# design.net
KiCad netlist of a schematic drawn in Altium Designer
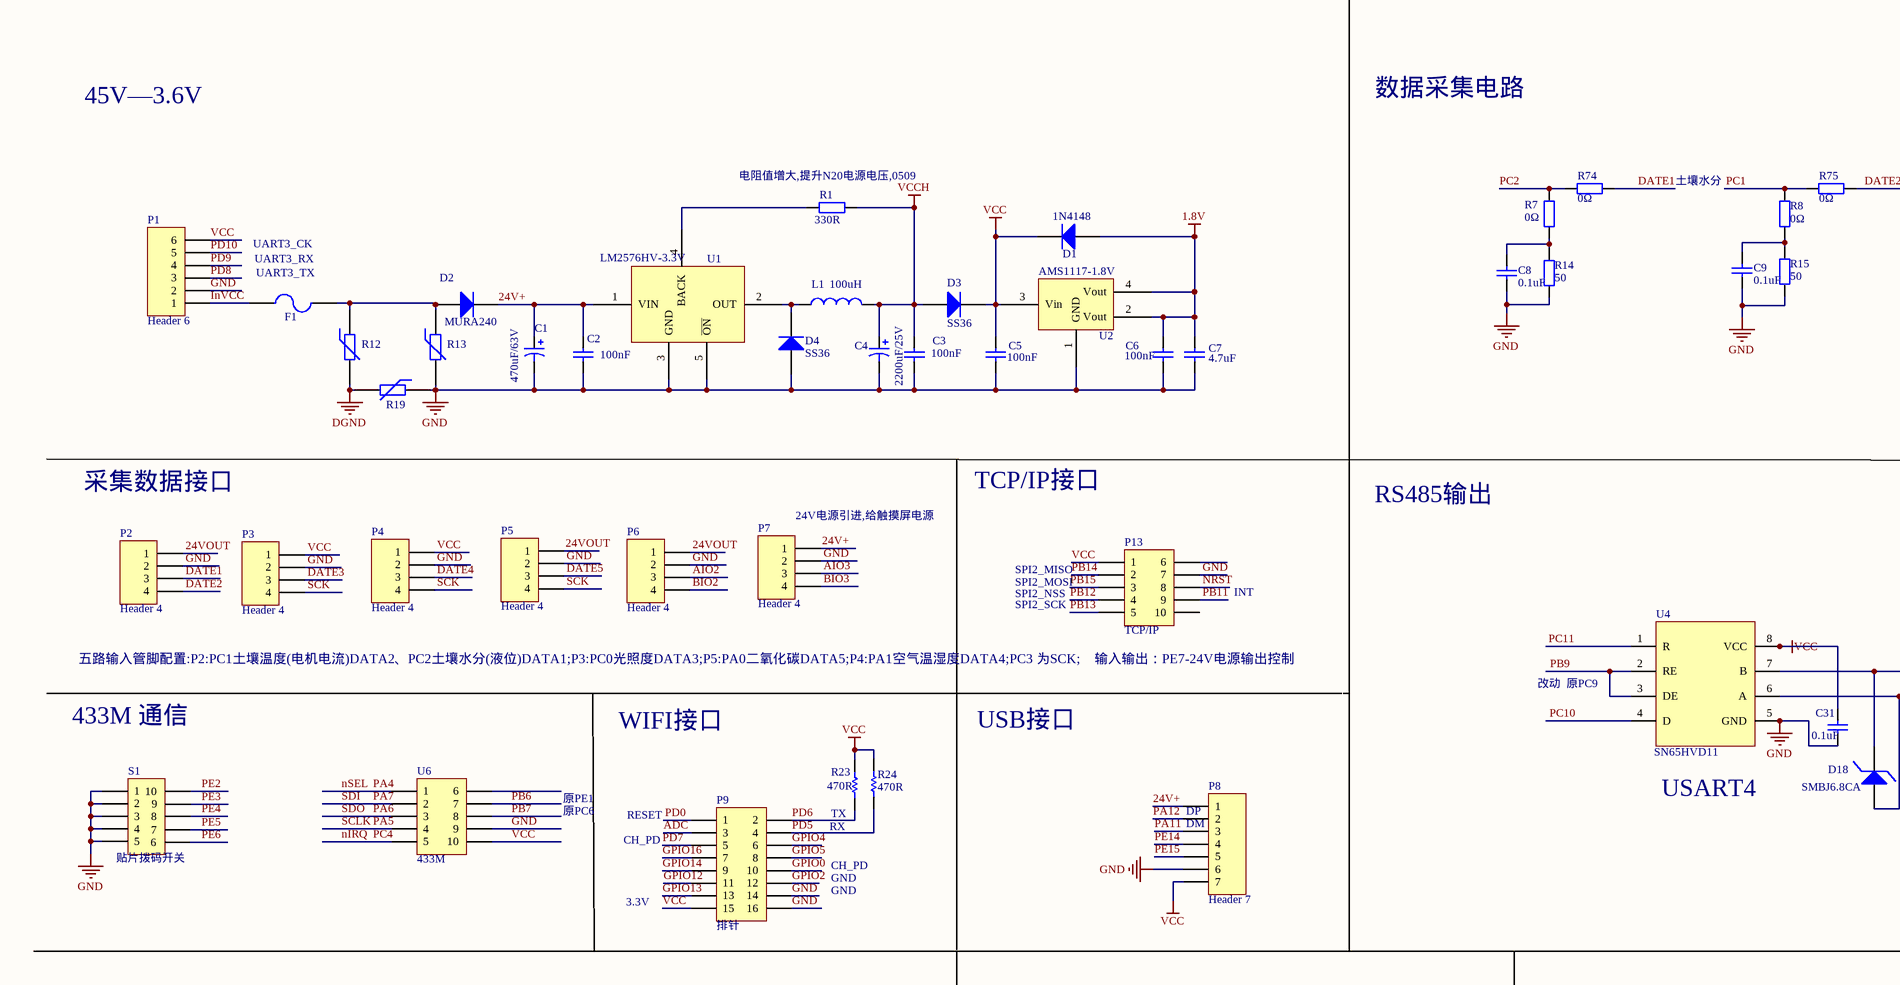
[diagram p0: 边缘网关一体.SchDoc, top left]
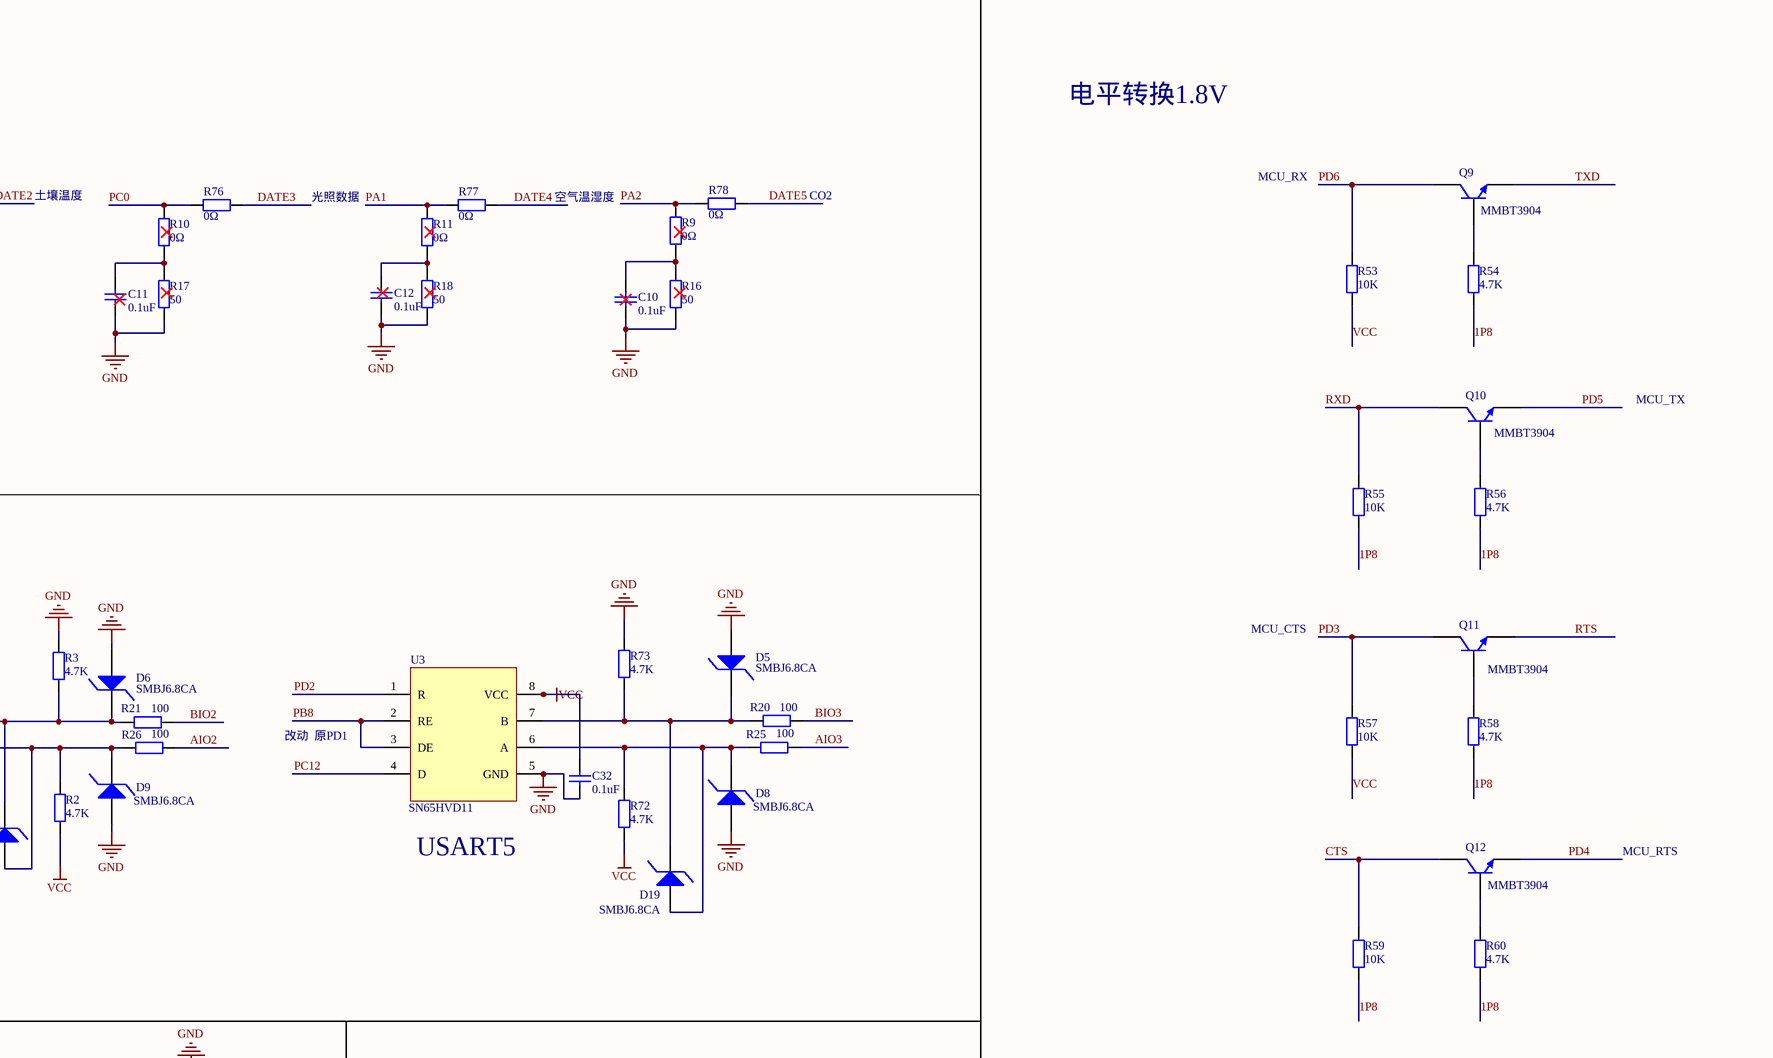
[diagram p1: 边缘网关一体.SchDoc, top right]
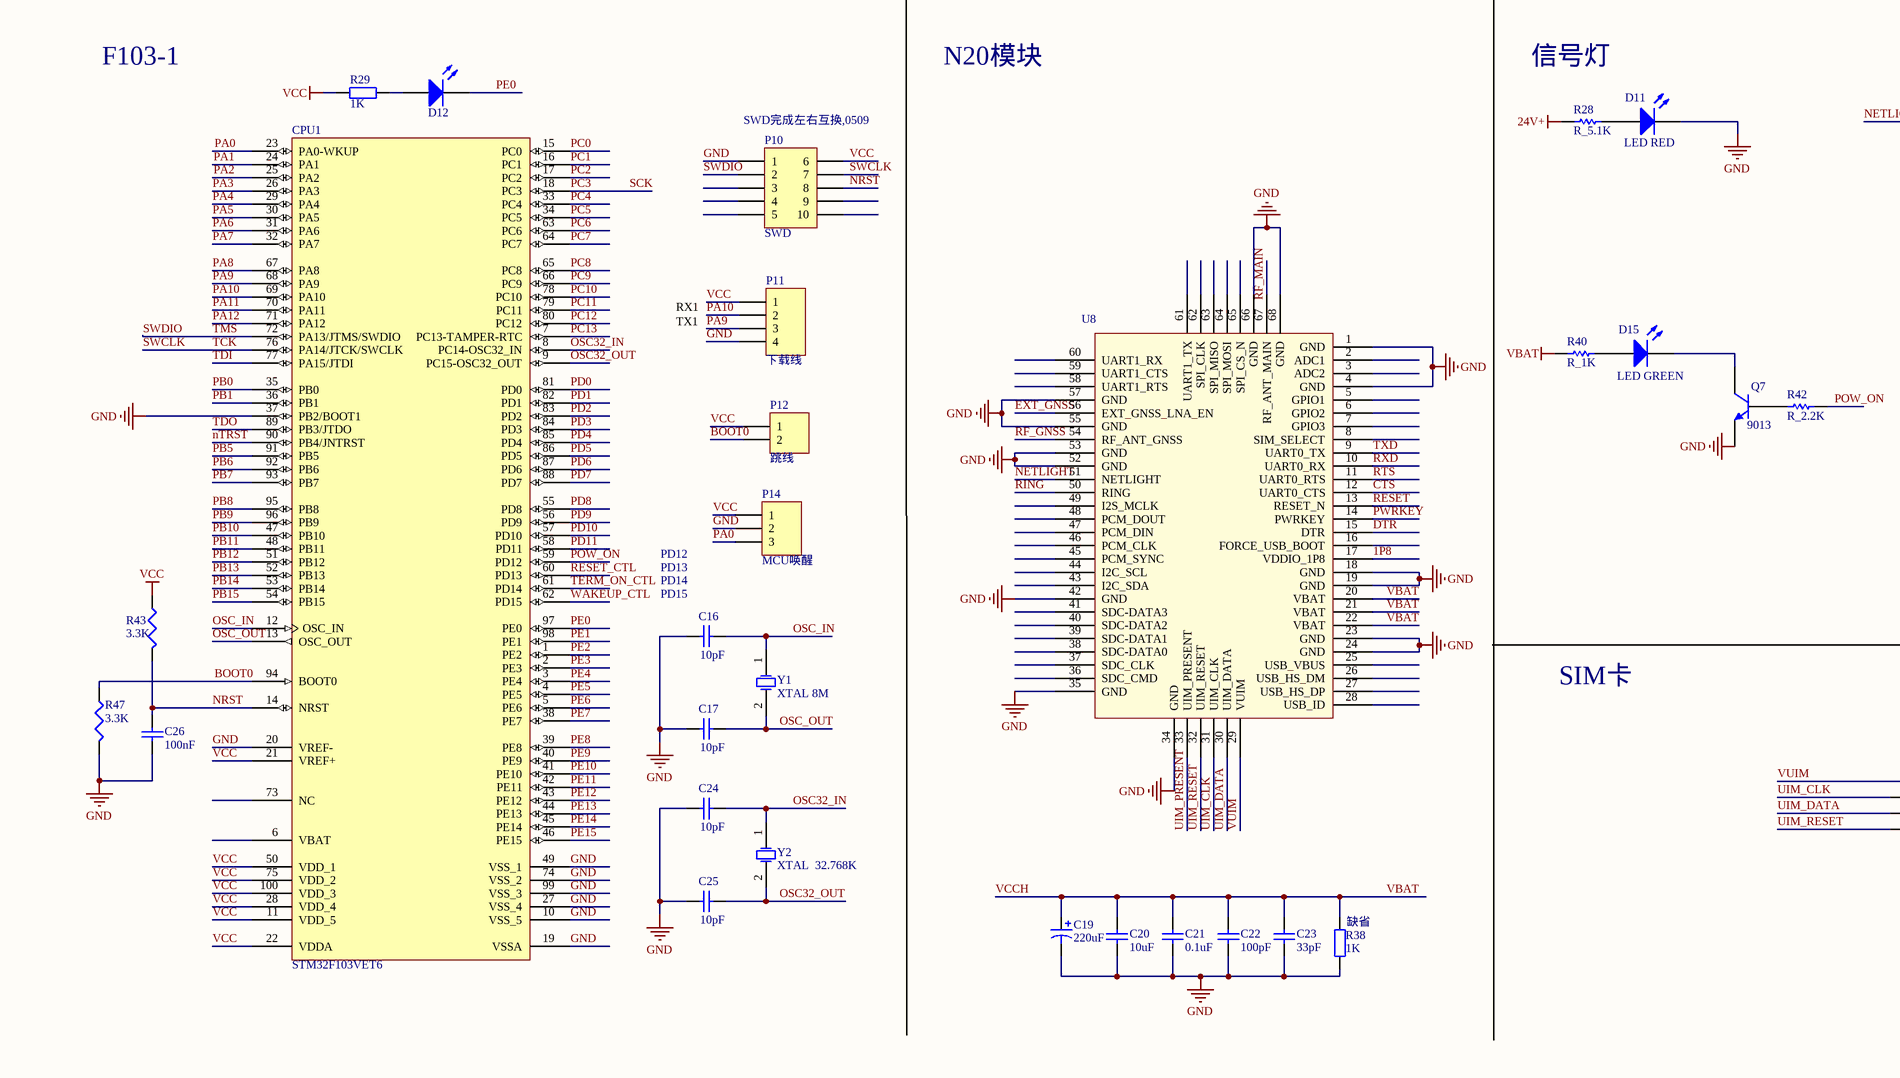
[diagram p2: 边缘网关一体.SchDoc, bottom left]
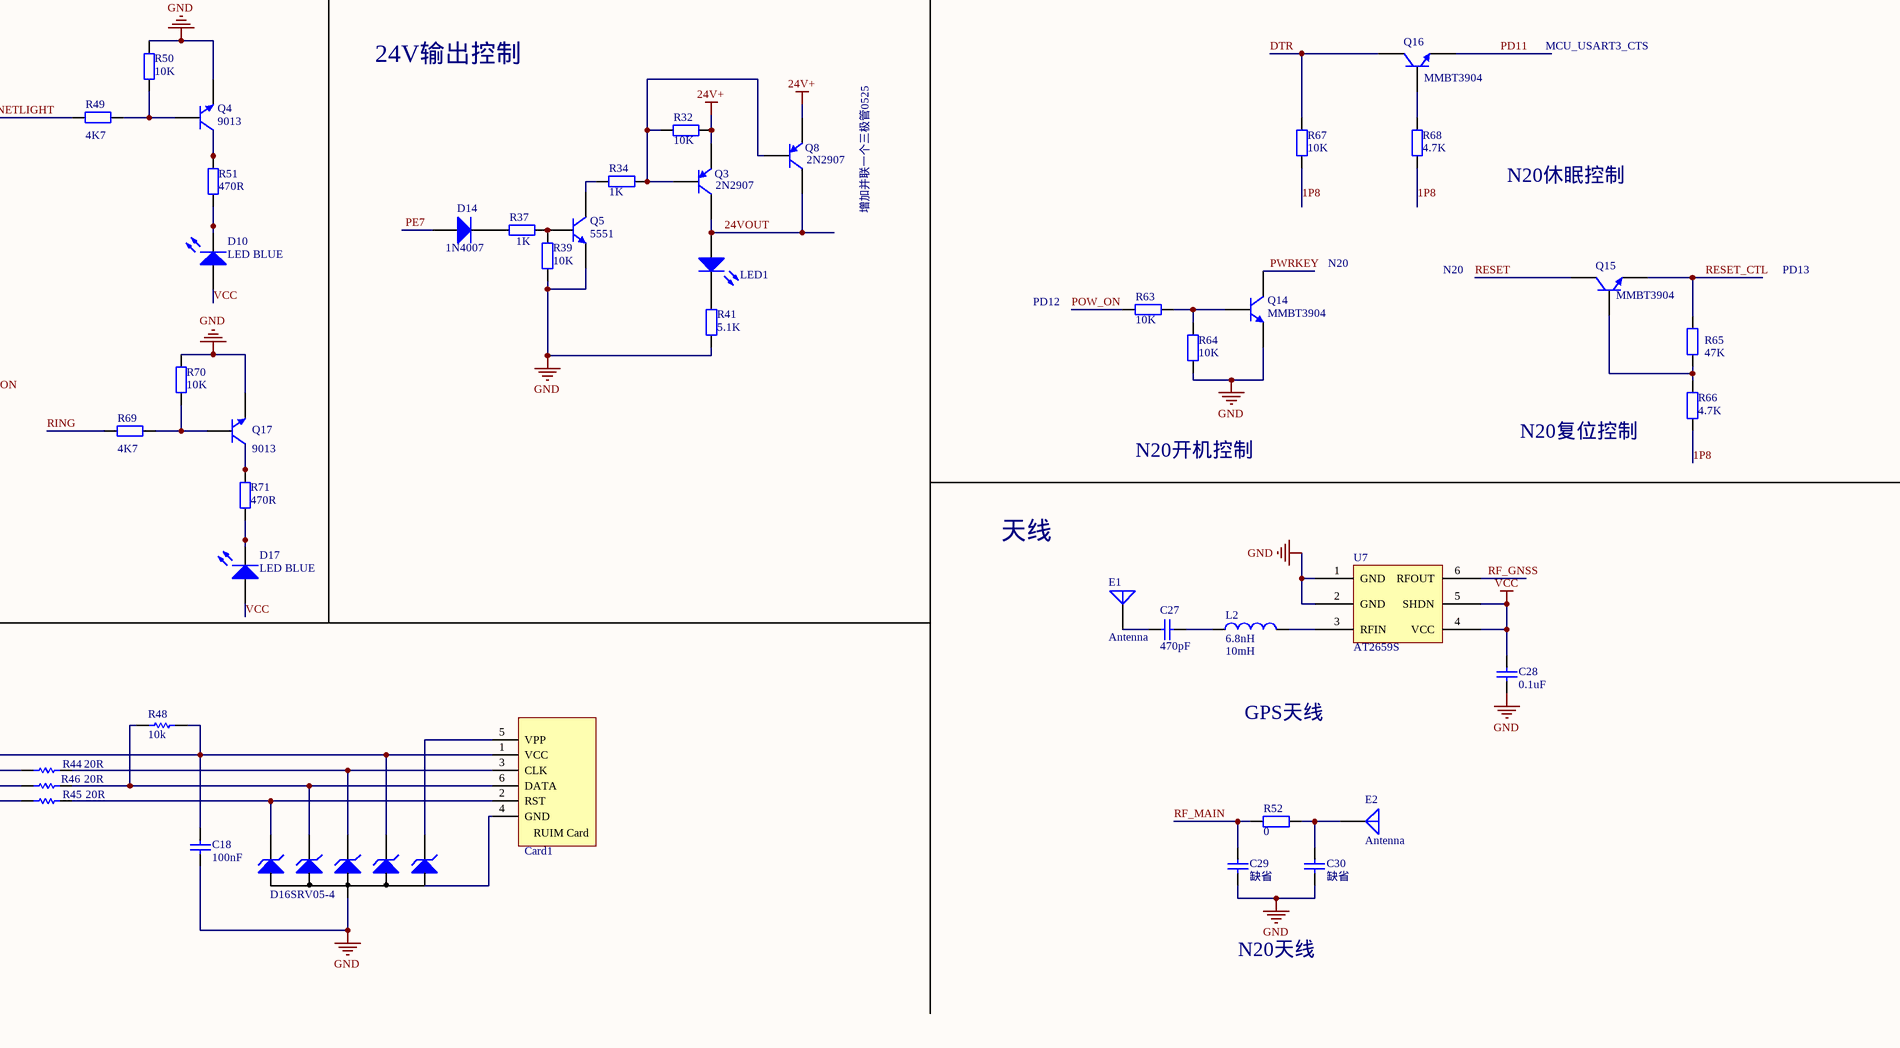
[diagram p3: 边缘网关一体.SchDoc, bottom right]

(export (version "E")
  (design (tool "Eeschema 10.0.6"))
  (components
    (comp (ref "C1")
      (value "470uF/63V")
      (footprint "C470UF50V-H")
      (description "插件 电解电容 13*21")
      (fields (field (name "Comment") "C_470uF/63V") (field (name "PUBLISHER") "Altium Limited"))
      (libsource (lib "Miscellaneous Devices") (part "Cap Pol1"))
    )
    (comp (ref "C2")
      (value "100nF")
      (footprint "0805")
      (description "贴片电容 0603")
      (fields (field (name "Comment") "C_0.1uF") (field (name "PUBLISHER") "Altium Limited"))
      (libsource (lib "Miscellaneous Devices") (part "Cap"))
    )
    (comp (ref "C3")
      (value "100nF")
      (footprint "0603")
      (description "贴片电容 0603")
      (fields (field (name "Comment") "C_0.1uF") (field (name "PUBLISHER") "Altium Limited"))
      (libsource (lib "Miscellaneous Devices") (part "Cap"))
    )
    (comp (ref "C4")
      (value "2200uF/25V")
      (footprint "C470UF50V-H")
      (description "插件 体积13*20mm")
      (fields (field (name "PUBLISHER") "Altium Limited"))
      (libsource (lib "Miscellaneous Devices") (part "Cap Pol1"))
    )
    (comp (ref "C5")
      (value "100nF")
      (footprint "0805")
      (description "贴片电容 0603")
      (fields (field (name "PUBLISHER") "Altium Limited"))
      (libsource (lib "Miscellaneous Devices") (part "Cap"))
    )
    (comp (ref "C6")
      (value "100nF")
      (footprint "0603")
      (description "贴片电容 0603")
      (fields (field (name "PUBLISHER") "Altium Limited"))
      (libsource (lib "Miscellaneous Devices") (part "Cap"))
    )
    (comp (ref "C7")
      (value "4.7uF")
      (footprint "0805")
      (description "贴片电容 0603")
      (libsource (lib "MyMiscellaneousDevices") (part "Cap"))
    )
    (comp (ref "C8")
      (value "0.1uF")
      (footprint "0603")
      (description "贴片电容 0603")
      (fields (field (name "Comment") "C_0.1uF") (field (name "PUBLISHER") "Altium Limited"))
      (libsource (lib "Miscellaneous Devices") (part "Cap"))
    )
    (comp (ref "C9")
      (value "0.1uF")
      (footprint "0603")
      (description "贴片电容 0603")
      (fields (field (name "Comment") "C_0.1uF") (field (name "PUBLISHER") "Altium Limited"))
      (libsource (lib "Miscellaneous Devices") (part "Cap"))
    )
    (comp (ref "C10")
      (value "0.1uF")
      (footprint "0603")
      (description "贴片电容 0603")
      (fields (field (name "Comment") "C_0.1uF") (field (name "PUBLISHER") "Altium Limited"))
      (libsource (lib "Miscellaneous Devices") (part "Cap"))
    )
    (comp (ref "C11")
      (value "0.1uF")
      (footprint "0603")
      (description "贴片电容 0603")
      (fields (field (name "Comment") "C_0.1uF") (field (name "PUBLISHER") "Altium Limited"))
      (libsource (lib "Miscellaneous Devices") (part "Cap"))
    )
    (comp (ref "C12")
      (value "0.1uF")
      (footprint "0603")
      (description "贴片电容 0603")
      (fields (field (name "Comment") "C_0.1uF") (field (name "PUBLISHER") "Altium Limited"))
      (libsource (lib "Miscellaneous Devices") (part "Cap"))
    )
    (comp (ref "C16")
      (value "10pF")
      (footprint "0603")
      (description "贴片电容 0603")
      (fields (field (name "Comment") "C_10pF") (field (name "PUBLISHER") "Altium Limited"))
      (libsource (lib "Miscellaneous Devices") (part "Cap"))
    )
    (comp (ref "C17")
      (value "10pF")
      (footprint "0603")
      (description "贴片电容 0603")
      (fields (field (name "Comment") "C_10pF") (field (name "PUBLISHER") "Altium Limited"))
      (libsource (lib "Miscellaneous Devices") (part "Cap"))
    )
    (comp (ref "C18")
      (value "100nF")
      (footprint "0805")
      (description "贴片电容 0603")
      (fields (field (name "Comment") "C_0.1uF") (field (name "PUBLISHER") "Altium Limited"))
      (libsource (lib "边缘网关一体17KF4") (part "Cap"))
    )
    (comp (ref "C19")
      (value "220uF")
      (footprint "1206")
      (description "Polarized Capacitor (Radial)")
      (fields (field (name "PUBLISHER") "Altium Limited"))
      (libsource (lib "Miscellaneous Devices") (part "Cap Pol1"))
    )
    (comp (ref "C20")
      (value "10uF")
      (footprint "0603")
      (description "贴片电容 0603")
      (fields (field (name "Comment") "C_0.1uF") (field (name "PUBLISHER") "Altium Limited"))
      (libsource (lib "Miscellaneous Devices") (part "Cap"))
    )
    (comp (ref "C21")
      (value "0.1uF")
      (footprint "0603")
      (description "贴片电容 0603")
      (fields (field (name "Comment") "C_0.1uF") (field (name "PUBLISHER") "Altium Limited"))
      (libsource (lib "Miscellaneous Devices") (part "Cap"))
    )
    (comp (ref "C22")
      (value "100pF")
      (footprint "0603")
      (description "贴片电容 0603")
      (fields (field (name "Comment") "C_0.1uF") (field (name "PUBLISHER") "Altium Limited"))
      (libsource (lib "Miscellaneous Devices") (part "Cap"))
    )
    (comp (ref "C23")
      (value "33pF")
      (footprint "0603")
      (description "贴片电容 0603")
      (fields (field (name "Comment") "C_0.1uF") (field (name "PUBLISHER") "Altium Limited"))
      (libsource (lib "Miscellaneous Devices") (part "Cap"))
    )
    (comp (ref "C24")
      (value "10pF")
      (footprint "0603")
      (description "贴片电容 0603")
      (fields (field (name "Comment") "C_10pF") (field (name "PUBLISHER") "Altium Limited"))
      (libsource (lib "Miscellaneous Devices") (part "Cap"))
    )
    (comp (ref "C25")
      (value "10pF")
      (footprint "0603")
      (description "贴片电容 0603")
      (fields (field (name "Comment") "C_10pF") (field (name "PUBLISHER") "Altium Limited"))
      (libsource (lib "Miscellaneous Devices") (part "Cap"))
    )
    (comp (ref "C26")
      (value "100nF")
      (footprint "0603")
      (description "贴片电容 0603")
      (fields (field (name "Comment") "C_100nF") (field (name "PUBLISHER") "Altium Limited"))
      (libsource (lib "Miscellaneous Devices") (part "Cap"))
    )
    (comp (ref "C27")
      (value "470pF")
      (footprint "1608[0603]")
      (description "Capacitor")
      (fields (field (name "PUBLISHER") "Altium Limited"))
      (libsource (lib "Miscellaneous Devices") (part "Cap"))
    )
    (comp (ref "C28")
      (value "0.1uF")
      (footprint "1608[0603]")
      (description "Capacitor")
      (fields (field (name "PUBLISHER") "Altium Limited"))
      (libsource (lib "Miscellaneous Devices") (part "Cap"))
    )
    (comp (ref "C29")
      (value "缺省")
      (footprint "0603")
      (description "Capacitor")
      (fields (field (name "PUBLISHER") "Altium Limited"))
      (libsource (lib "Miscellaneous Devices") (part "Cap"))
    )
    (comp (ref "C30")
      (value "缺省")
      (footprint "0603")
      (description "Capacitor")
      (fields (field (name "PUBLISHER") "Altium Limited"))
      (libsource (lib "Miscellaneous Devices") (part "Cap"))
    )
    (comp (ref "C31")
      (value "0.1uF")
      (footprint "0603")
      (description "Capacitor")
      (fields (field (name "PUBLISHER") "Altium Limited"))
      (libsource (lib "Miscellaneous Devices") (part "Cap"))
    )
    (comp (ref "C32")
      (value "0.1uF")
      (footprint "0603")
      (description "Capacitor")
      (fields (field (name "PUBLISHER") "Altium Limited"))
      (libsource (lib "Miscellaneous Devices") (part "Cap"))
    )
    (comp (ref "Card1") (value "Card") (footprint "SIM") (libsource (lib "ZDHH") (part "Card")))
    (comp (ref "CPU1")
      (value "STM32F103VET6")
      (footprint "LQFP100_N")
      (description "贴片ARM芯片")
      (fields (field (name "PUBLISHER") "Altium Limited"))
      (libsource (lib "ST Microcontroller 32-Bit STM32") (part "STM32F103VBT6"))
    )
    (comp (ref "D1")
      (value "1N4148")
      (footprint "1206")
      (description "贴片二极管 M7")
      (fields (field (name "PUBLISHER") "Altium Limited"))
      (libsource (lib "") (part "Diode_1"))
    )
    (comp (ref "D2")
      (value "MURA240")
      (footprint "1N4007-M7")
      (description "贴片二极管 M7")
      (fields (field (name "PUBLISHER") "Altium Limited"))
      (libsource (lib "Miscellaneous Devices") (part "Diode"))
    )
    (comp (ref "D3")
      (value "SS36")
      (footprint "1N4007-M7")
      (description "贴片二极管 SMA")
      (fields (field (name "PUBLISHER") "Altium Limited"))
      (libsource (lib "Miscellaneous Devices") (part "Diode 1N4007"))
    )
    (comp (ref "D4")
      (value "SS36")
      (footprint "1N4007-M7")
      (description "贴片二极管 SMA")
      (fields (field (name "PUBLISHER") "Altium Limited"))
      (libsource (lib "Miscellaneous Devices") (part "Diode 1N4007"))
    )
    (comp (ref "D5")
      (value "SMBJ6.8CA")
      (footprint "DO-214AB")
      (description "贴片双向瞬变抑制二极管 D0-214AA")
      (libsource (lib "User Library") (part "SMBJ6.8CA"))
    )
    (comp (ref "D6")
      (value "SMBJ6.8CA")
      (footprint "DO-214AB")
      (description "贴片双向瞬变抑制二极管 D0-214AA")
      (libsource (lib "User Library") (part "SMBJ6.8CA"))
    )
    (comp (ref "D8")
      (value "SMBJ6.8CA")
      (footprint "DO-214AB")
      (description "贴片双向瞬变抑制二极管 D0-214AA")
      (libsource (lib "User Library") (part "SMBJ6.8CA"))
    )
    (comp (ref "D9")
      (value "SMBJ6.8CA")
      (footprint "DO-214AB")
      (description "贴片双向瞬变抑制二极管 D0-214AA")
      (libsource (lib "User Library") (part "SMBJ6.8CA"))
    )
    (comp (ref "D10")
      (value "LED BLUE")
      (footprint "LED-3mm")
      (description "插件 发光二极管 5mm 红发红光")
      (fields (field (name "PUBLISHER") "Altium Limited"))
      (libsource (lib "Miscellaneous Devices") (part "LED0"))
    )
    (comp (ref "D11")
      (value "LED RED")
      (footprint "LED-3mm")
      (description "插件 发光二极管 5mm 红发红光")
      (fields (field (name "PUBLISHER") "Altium Limited"))
      (libsource (lib "Miscellaneous Devices") (part "LED0"))
    )
    (comp (ref "D12")
      (value "Green")
      (footprint "0603")
      (description "贴片发光二极管 0603 绿色")
      (libsource (lib "Schlib-user") (part "LED 3mm"))
    )
    (comp (ref "D14")
      (value "1N4007")
      (footprint "1N4007-M7")
      (description "1 Amp General Purpose Rectifier")
      (fields (field (name "PUBLISHER") "Altium Limited"))
      (libsource (lib "Miscellaneous Devices") (part "Diode 1N4007"))
    )
    (comp (ref "D15")
      (value "LED GREEN")
      (footprint "LED-3mm")
      (description "插件 发光二极管 5mm 绿发绿光")
      (fields (field (name "PUBLISHER") "Altium Limited"))
      (libsource (lib "Miscellaneous Devices") (part "LED0"))
    )
    (comp (ref "D16")
      (value "SRV05-4")
      (footprint "SOT23-6")
      (description "SOT363")
      (fields (field (name "PUBLISHER") "Altium Limited"))
      (libsource (lib "SCHLIB") (part "SMF05C"))
    )
    (comp (ref "D17")
      (value "LED BLUE")
      (footprint "LED-3mm")
      (description "插件 发光二极管 5mm 红发红光")
      (fields (field (name "PUBLISHER") "Altium Limited"))
      (libsource (lib "Miscellaneous Devices") (part "LED0"))
    )
    (comp (ref "D18")
      (value "SMBJ6.8CA")
      (footprint "DO-214AB")
      (description "贴片双向瞬变抑制二极管 D0-214AA")
      (libsource (lib "User Library") (part "SMBJ6.8CA"))
    )
    (comp (ref "D19")
      (value "SMBJ6.8CA")
      (footprint "DO-214AB")
      (description "贴片双向瞬变抑制二极管 D0-214AA")
      (libsource (lib "User Library") (part "SMBJ6.8CA"))
    )
    (comp (ref "E1")
      (value "Antenna")
      (footprint "IPX")
      (description "Generic Antenna")
      (fields (field (name "PUBLISHER") "Altium Limited"))
      (libsource (lib "Miscellaneous Devices") (part "Antenna"))
    )
    (comp (ref "E2")
      (value "Antenna")
      (footprint "IPX")
      (description "Generic Antenna")
      (fields (field (name "PUBLISHER") "Altium Limited"))
      (libsource (lib "Miscellaneous Devices") (part "Antenna"))
    )
    (comp (ref "F1")
      (value "自恢复保险丝")
      (footprint "1812")
      (description "1812 1.1A 33V")
      (fields (field (name "PUBLISHER") "Altium Limited"))
      (libsource (lib "Miscellaneous Devices") (part "Fuse 2"))
    )
    (comp (ref "L1")
      (value "100uH")
      (footprint "L101")
      (description "贴片电感 12*12*7mm 100uH")
      (fields (field (name "Comment") "贴片电感") (field (name "PUBLISHER") "Altium Limited"))
      (libsource (lib "Miscellaneous Devices") (part "Inductor"))
    )
    (comp (ref "L2")
      (value "6.8nH")
      (footprint "L0603")
      (description "Inductor")
      (fields (field (name "ALTIUM_VALUE") "10mH") (field (name "PUBLISHER") "Altium Limited"))
      (libsource (lib "Miscellaneous Devices") (part "Inductor"))
    )
    (comp (ref "LED1")
      (value "LED 3mm")
      (footprint "0603")
      (description "LED_R")
      (libsource (lib "Schlib-user") (part "LED 3mm"))
    )
    (comp (ref "P1")
      (value "Header 6")
      (footprint "P6HEADER:PCBComponent_1")
      (description "Header, 6-Pin")
      (fields (field (name "PUBLISHER") "Altium Limited"))
      (libsource (lib "Miscellaneous Connectors") (part "Header 6"))
    )
    (comp (ref "P2")
      (value "Header 4")
      (footprint "HDR1X4")
      (description "Header, 4-Pin")
      (fields (field (name "PUBLISHER") "Altium Limited"))
      (libsource (lib "Miscellaneous Connectors") (part "Header 4"))
    )
    (comp (ref "P3")
      (value "Header 4")
      (footprint "HDR1X4")
      (description "Header, 4-Pin")
      (fields (field (name "PUBLISHER") "Altium Limited"))
      (libsource (lib "Miscellaneous Connectors") (part "Header 4"))
    )
    (comp (ref "P4")
      (value "Header 4")
      (footprint "HDR1X4")
      (description "Header, 4-Pin")
      (fields (field (name "PUBLISHER") "Altium Limited"))
      (libsource (lib "Miscellaneous Connectors") (part "Header 4"))
    )
    (comp (ref "P5")
      (value "Header 4")
      (footprint "HDR1X4")
      (description "Header, 4-Pin")
      (fields (field (name "PUBLISHER") "Altium Limited"))
      (libsource (lib "Miscellaneous Connectors") (part "Header 4"))
    )
    (comp (ref "P6")
      (value "Header 4")
      (footprint "HDR1X4")
      (description "Header, 4-Pin")
      (fields (field (name "PUBLISHER") "Altium Limited"))
      (libsource (lib "Miscellaneous Connectors") (part "Header 4"))
    )
    (comp (ref "P7")
      (value "Header 4")
      (footprint "HDR1X4")
      (description "Header, 4-Pin")
      (fields (field (name "PUBLISHER") "Altium Limited"))
      (libsource (lib "Miscellaneous Connectors") (part "Header 4"))
    )
    (comp (ref "P8")
      (value "Header 7")
      (footprint "USB2")
      (description "Header, 7-Pin")
      (fields (field (name "PUBLISHER") "Altium Limited"))
      (libsource (lib "Miscellaneous Connectors") (part "Header 7"))
    )
    (comp (ref "P9")
      (value "排针")
      (footprint "WIFI2")
      (description "插件 8P 间距2mm")
      (fields (field (name "PUBLISHER") "Altium Limited"))
      (libsource (lib "Miscellaneous Connectors") (part "Header 8X2"))
    )
    (comp (ref "P10")
      (value "SWD")
      (footprint "HDR2X5_CEN")
      (description "Header, 5-Pin, Dual row")
      (fields (field (name "PUBLISHER") "Altium Limited"))
      (libsource (lib "Miscellaneous Connectors") (part "Header 5X2A"))
    )
    (comp (ref "P11")
      (value "下载线")
      (footprint "HDR1X4")
      (description "Header, 4-Pin")
      (fields (field (name "PUBLISHER") "Altium Limited"))
      (libsource (lib "") (part "Header 4_1"))
    )
    (comp (ref "P12")
      (value "跳线")
      (footprint "HDR1X2")
      (description "Header, 2-Pin")
      (fields (field (name "PUBLISHER") "Altium Limited"))
      (libsource (lib "Miscellaneous Connectors") (part "Header 2"))
    )
    (comp (ref "P13")
      (value "TCP/IP")
      (footprint "TCP-IP")
      (description "Header, 5-Pin, Dual row")
      (fields (field (name "PUBLISHER") "Altium Limited"))
      (libsource (lib "Miscellaneous Connectors") (part "Header 5X2A"))
    )
    (comp (ref "P14")
      (value "MCU唤醒")
      (footprint "HDR1X3")
      (description "Header, 3-Pin")
      (fields (field (name "PUBLISHER") "Altium Limited"))
      (libsource (lib "Miscellaneous Connectors") (part "Header 3"))
    )
    (comp (ref "Q3")
      (value "2N2907")
      (footprint "Q")
      (description "PNP Bipolar Transistor")
      (fields (field (name "PUBLISHER") "Altium Limited"))
      (libsource (lib "Miscellaneous Devices") (part "PNP"))
    )
    (comp (ref "Q4")
      (value "9013")
      (footprint "SOT-23")
      (description "贴片三极管MMBT5551 SOT-23")
      (fields (field (name "PUBLISHER") "Altium Limited"))
      (libsource (lib "MyMiscellaneousDevices") (part "NPN"))
    )
    (comp (ref "Q5")
      (value "5551")
      (footprint "Q")
      (description "2N3904")
      (fields (field (name "PUBLISHER") "Altium Limited"))
      (libsource (lib "Miscellaneous Devices") (part "2N3904"))
    )
    (comp (ref "Q7")
      (value "9013")
      (footprint "SOT-23")
      (description "贴片三极管MMBT5551 SOT-23")
      (fields (field (name "PUBLISHER") "Altium Limited"))
      (libsource (lib "MyMiscellaneousDevices") (part "NPN"))
    )
    (comp (ref "Q8")
      (value "2N2907")
      (footprint "Q")
      (description "PNP Bipolar Transistor")
      (fields (field (name "PUBLISHER") "Altium Limited"))
      (libsource (lib "Miscellaneous Devices") (part "PNP"))
    )
    (comp (ref "Q9")
      (value "MMBT3904")
      (footprint "SOT23_N")
      (description "NPN Switching Transistor")
      (fields (field (name "PUBLISHER") "Altium Limited"))
      (libsource (lib "Philips Discrete BJT - Low Power") (part "MMBT3904"))
    )
    (comp (ref "Q10")
      (value "MMBT3904")
      (footprint "SOT23_N")
      (description "NPN Switching Transistor")
      (fields (field (name "PUBLISHER") "Altium Limited"))
      (libsource (lib "Philips Discrete BJT - Low Power") (part "MMBT3904"))
    )
    (comp (ref "Q11")
      (value "MMBT3904")
      (footprint "SOT23_N")
      (description "NPN Switching Transistor")
      (fields (field (name "PUBLISHER") "Altium Limited"))
      (libsource (lib "Philips Discrete BJT - Low Power") (part "MMBT3904"))
    )
    (comp (ref "Q12")
      (value "MMBT3904")
      (footprint "SOT23_N")
      (description "NPN Switching Transistor")
      (fields (field (name "PUBLISHER") "Altium Limited"))
      (libsource (lib "Philips Discrete BJT - Low Power") (part "MMBT3904"))
    )
    (comp (ref "Q14")
      (value "MMBT3904")
      (footprint "SOT23_N")
      (description "NPN Switching Transistor")
      (fields (field (name "PUBLISHER") "Altium Limited"))
      (libsource (lib "Philips Discrete BJT - Low Power") (part "MMBT3904"))
    )
    (comp (ref "Q15")
      (value "MMBT3904")
      (footprint "SOT23_N")
      (description "NPN Switching Transistor")
      (fields (field (name "PUBLISHER") "Altium Limited"))
      (libsource (lib "Philips Discrete BJT - Low Power") (part "MMBT3904"))
    )
    (comp (ref "Q16")
      (value "MMBT3904")
      (footprint "SOT23_N")
      (description "NPN Switching Transistor")
      (fields (field (name "PUBLISHER") "Altium Limited"))
      (libsource (lib "Philips Discrete BJT - Low Power") (part "MMBT3904"))
    )
    (comp (ref "Q17")
      (value "9013")
      (footprint "SOT-23")
      (description "贴片三极管MMBT5551 SOT-23")
      (fields (field (name "PUBLISHER") "Altium Limited"))
      (libsource (lib "MyMiscellaneousDevices") (part "NPN"))
    )
    (comp (ref "R1")
      (value "330R")
      (footprint "0805")
      (description "贴片电阻 0805 精度0.1%")
      (fields (field (name "PUBLISHER") "Altium Limited"))
      (libsource (lib "") (part "Res2_2"))
    )
    (comp (ref "R2")
      (value "4.7K")
      (footprint "0603")
      (description "贴片电阻 0603")
      (fields (field (name "PUBLISHER") "Altium Limited"))
      (libsource (lib "") (part "Res2_3"))
    )
    (comp (ref "R3")
      (value "4.7K")
      (footprint "0603")
      (description "贴片电阻 0603")
      (fields (field (name "Comment") "100R") (field (name "PUBLISHER") "Altium Limited"))
      (libsource (lib "Miscellaneous Devices") (part "Res2"))
    )
    (comp (ref "R7")
      (value "0Ω")
      (footprint "0805")
      (description "贴片电阻 0805 精度0.1%")
      (fields (field (name "Comment") "50R") (field (name "PUBLISHER") "Altium Limited"))
      (libsource (lib "Miscellaneous Devices") (part "Res2"))
    )
    (comp (ref "R8")
      (value "0Ω")
      (footprint "0805")
      (description "贴片电阻 0805 精度0.1%")
      (fields (field (name "Comment") "50R") (field (name "PUBLISHER") "Altium Limited"))
      (libsource (lib "Miscellaneous Devices") (part "Res2"))
    )
    (comp (ref "R9")
      (value "0Ω")
      (footprint "0805")
      (description "贴片电阻 0805 精度0.1%")
      (fields (field (name "Comment") "50R") (field (name "PUBLISHER") "Altium Limited"))
      (libsource (lib "Miscellaneous Devices") (part "Res2"))
    )
    (comp (ref "R10")
      (value "0Ω")
      (footprint "0805")
      (description "贴片电阻 0805 精度0.1%")
      (fields (field (name "Comment") "50R") (field (name "PUBLISHER") "Altium Limited"))
      (libsource (lib "Miscellaneous Devices") (part "Res2"))
    )
    (comp (ref "R11")
      (value "0Ω")
      (footprint "0805")
      (description "贴片电阻 0805 精度0.1%")
      (fields (field (name "Comment") "50R") (field (name "PUBLISHER") "Altium Limited"))
      (libsource (lib "Miscellaneous Devices") (part "Res2"))
    )
    (comp (ref "R12")
      (value "压敏电阻")
      (footprint "0805")
      (description "耐压56V 0805")
      (fields (field (name "PUBLISHER") "Altium Limited"))
      (libsource (lib "Miscellaneous Devices") (part "Res Varistor"))
    )
    (comp (ref "R13")
      (value "压敏电阻")
      (footprint "0805")
      (description "耐压56V 0805")
      (fields (field (name "PUBLISHER") "Altium Limited"))
      (libsource (lib "Miscellaneous Devices") (part "Res Varistor"))
    )
    (comp (ref "R14")
      (value "50")
      (footprint "0805")
      (description "贴片电阻 0805 精度0.1%")
      (fields (field (name "Comment") "50R") (field (name "PUBLISHER") "Altium Limited"))
      (libsource (lib "Miscellaneous Devices") (part "Res2"))
    )
    (comp (ref "R15")
      (value "50")
      (footprint "0805")
      (description "贴片电阻 0805 精度0.1%")
      (fields (field (name "Comment") "50R") (field (name "PUBLISHER") "Altium Limited"))
      (libsource (lib "") (part "Res2_3"))
    )
    (comp (ref "R16")
      (value "50")
      (footprint "0805")
      (description "贴片电阻 0805 精度0.1%")
      (fields (field (name "Comment") "50R") (field (name "PUBLISHER") "Altium Limited"))
      (libsource (lib "") (part "Res2_3"))
    )
    (comp (ref "R17")
      (value "50")
      (footprint "0805")
      (description "贴片电阻 0805 精度0.1%")
      (fields (field (name "Comment") "50R") (field (name "PUBLISHER") "Altium Limited"))
      (libsource (lib "") (part "Res2_3"))
    )
    (comp (ref "R18")
      (value "50")
      (footprint "0805")
      (description "贴片电阻 0805 精度0.1%")
      (fields (field (name "Comment") "50R") (field (name "PUBLISHER") "Altium Limited"))
      (libsource (lib "") (part "Res2_3"))
    )
    (comp (ref "R19")
      (value "压敏电阻")
      (footprint "0805")
      (description "耐压56V 0805")
      (fields (field (name "PUBLISHER") "Altium Limited"))
      (libsource (lib "Miscellaneous Devices") (part "Res Varistor"))
    )
    (comp (ref "R20")
      (value "100")
      (footprint "0603")
      (description "贴片电阻 0603")
      (fields (field (name "Comment") "100R") (field (name "PUBLISHER") "Altium Limited"))
      (libsource (lib "") (part "Res2_1"))
    )
    (comp (ref "R21")
      (value "100")
      (footprint "0603")
      (description "贴片电阻 0603")
      (fields (field (name "Comment") "100R") (field (name "PUBLISHER") "Altium Limited"))
      (libsource (lib "") (part "Res2_1"))
    )
    (comp (ref "R23")
      (value "470R")
      (footprint "0603")
      (description "贴片电阻 0603")
      (fields (field (name "PUBLISHER") "Altium Limited"))
      (libsource (lib "Miscellaneous Devices") (part "Res1"))
    )
    (comp (ref "R24")
      (value "470R")
      (footprint "0603")
      (description "贴片电阻 0603")
      (fields (field (name "PUBLISHER") "Altium Limited"))
      (libsource (lib "Miscellaneous Devices") (part "Res1"))
    )
    (comp (ref "R25")
      (value "100")
      (footprint "0603")
      (description "贴片电阻 0603")
      (fields (field (name "Comment") "100R") (field (name "PUBLISHER") "Altium Limited"))
      (libsource (lib "") (part "Res2_1"))
    )
    (comp (ref "R26")
      (value "100")
      (footprint "0603")
      (description "贴片电阻 0603")
      (fields (field (name "Comment") "100R") (field (name "PUBLISHER") "Altium Limited"))
      (libsource (lib "") (part "Res2_1"))
    )
    (comp (ref "R28")
      (value "R_5.1K")
      (footprint "0603")
      (description "贴片电阻 0603")
      (libsource (lib "MyMiscellaneousDevices") (part "Resistor"))
    )
    (comp (ref "R29")
      (value "1K")
      (footprint "0603")
      (description "贴片电阻 0603")
      (fields (field (name "Comment") "R_1K") (field (name "PUBLISHER") "Altium Limited"))
      (libsource (lib "") (part "Res2_2"))
    )
    (comp (ref "R32")
      (value "10K")
      (footprint "0603")
      (description "Resistor")
      (fields (field (name "Comment") "R_10K") (field (name "PUBLISHER") "Altium Limited"))
      (libsource (lib "") (part "Res2_2"))
    )
    (comp (ref "R34")
      (value "1K")
      (footprint "0603")
      (description "Resistor")
      (fields (field (name "Comment") "R_1K") (field (name "PUBLISHER") "Altium Limited"))
      (libsource (lib "") (part "Res2_2"))
    )
    (comp (ref "R37")
      (value "1K")
      (footprint "0603")
      (description "Resistor")
      (fields (field (name "Comment") "R_1K") (field (name "PUBLISHER") "Altium Limited"))
      (libsource (lib "") (part "Res2_1"))
    )
    (comp (ref "R38")
      (value "缺省")
      (footprint "0603")
      (description "Resistor")
      (fields (field (name "ALTIUM_VALUE") "1K") (field (name "PUBLISHER") "Altium Limited"))
      (libsource (lib "Miscellaneous Devices") (part "Res2"))
    )
    (comp (ref "R39")
      (value "10K")
      (footprint "0603")
      (description "Resistor")
      (fields (field (name "Comment") "R_10K") (field (name "PUBLISHER") "Altium Limited"))
      (libsource (lib "Miscellaneous Devices") (part "Res2"))
    )
    (comp (ref "R40")
      (value "R_1K")
      (footprint "0603")
      (description "Resistor")
      (libsource (lib "MyMiscellaneousDevices") (part "Resistor"))
    )
    (comp (ref "R41")
      (value "5.1K")
      (footprint "0603")
      (description "R_10K")
      (fields (field (name "Comment") "R_5.1K") (field (name "PUBLISHER") "Altium Limited"))
      (libsource (lib "") (part "Res2_3"))
    )
    (comp (ref "R42")
      (value "R_2.2K")
      (footprint "0603")
      (description "Resistor")
      (libsource (lib "MyMiscellaneousDevices") (part "Resistor"))
    )
    (comp (ref "R43")
      (value "3.3K")
      (footprint "0603")
      (description "贴片电阻 0603")
      (fields (field (name "Comment") "R_3.3K") (field (name "PUBLISHER") "Altium Limited"))
      (libsource (lib "Miscellaneous Devices") (part "Res3"))
    )
    (comp (ref "R44")
      (value "20R")
      (footprint "0603")
      (description "贴片电阻 0603")
      (libsource (lib "Any") (part "Resistor"))
    )
    (comp (ref "R45")
      (value "20R")
      (footprint "0603")
      (description "贴片电阻 0603")
      (libsource (lib "MyMiscellaneousDevices") (part "Resistor"))
    )
    (comp (ref "R46")
      (value "20R")
      (footprint "0603")
      (description "贴片电阻 0603")
      (libsource (lib "Any") (part "Resistor"))
    )
    (comp (ref "R47")
      (value "3.3K")
      (footprint "0603")
      (description "贴片电阻 0603")
      (fields (field (name "Comment") "R_3.3K") (field (name "PUBLISHER") "Altium Limited"))
      (libsource (lib "Miscellaneous Devices") (part "Res3"))
    )
    (comp (ref "R48")
      (value "10k")
      (footprint "0603")
      (description "贴片电阻 0603")
      (fields (field (name "Comment") "470R") (field (name "PUBLISHER") "Altium Limited"))
      (libsource (lib "边缘网关一体17KF4") (part "Res1"))
    )
    (comp (ref "R49")
      (value "4K7")
      (footprint "0603")
      (description "Resistor")
      (fields (field (name "Comment") "Res2") (field (name "PUBLISHER") "Altium Limited"))
      (libsource (lib "") (part "Res2_1"))
    )
    (comp (ref "R50")
      (value "10K")
      (footprint "0603")
      (description "Resistor")
      (fields (field (name "Comment") "Res2") (field (name "PUBLISHER") "Altium Limited"))
      (libsource (lib "Miscellaneous Devices") (part "Res2"))
    )
    (comp (ref "R51")
      (value "470R")
      (footprint "0603")
      (description "Resistor")
      (fields (field (name "Comment") "Res2") (field (name "PUBLISHER") "Altium Limited"))
      (libsource (lib "") (part "Res2_3"))
    )
    (comp (ref "R52")
      (value "0")
      (footprint "0603")
      (description "Resistor")
      (fields (field (name "PUBLISHER") "Altium Limited"))
      (libsource (lib "") (part "Res2_1"))
    )
    (comp (ref "R53")
      (value "10K")
      (footprint "0603")
      (description "Resistor")
      (fields (field (name "PUBLISHER") "Altium Limited"))
      (libsource (lib "Miscellaneous Devices") (part "Res2"))
    )
    (comp (ref "R54")
      (value "4.7K")
      (footprint "0603")
      (description "Resistor")
      (fields (field (name "PUBLISHER") "Altium Limited"))
      (libsource (lib "Miscellaneous Devices") (part "Res2"))
    )
    (comp (ref "R55")
      (value "10K")
      (footprint "0603")
      (description "Resistor")
      (fields (field (name "PUBLISHER") "Altium Limited"))
      (libsource (lib "Miscellaneous Devices") (part "Res2"))
    )
    (comp (ref "R56")
      (value "4.7K")
      (footprint "0603")
      (description "Resistor")
      (fields (field (name "PUBLISHER") "Altium Limited"))
      (libsource (lib "Miscellaneous Devices") (part "Res2"))
    )
    (comp (ref "R57")
      (value "10K")
      (footprint "0603")
      (description "Resistor")
      (fields (field (name "PUBLISHER") "Altium Limited"))
      (libsource (lib "Miscellaneous Devices") (part "Res2"))
    )
    (comp (ref "R58")
      (value "4.7K")
      (footprint "0603")
      (description "Resistor")
      (fields (field (name "PUBLISHER") "Altium Limited"))
      (libsource (lib "Miscellaneous Devices") (part "Res2"))
    )
    (comp (ref "R59")
      (value "10K")
      (footprint "0603")
      (description "Resistor")
      (fields (field (name "PUBLISHER") "Altium Limited"))
      (libsource (lib "Miscellaneous Devices") (part "Res2"))
    )
    (comp (ref "R60")
      (value "4.7K")
      (footprint "0603")
      (description "Resistor")
      (fields (field (name "PUBLISHER") "Altium Limited"))
      (libsource (lib "Miscellaneous Devices") (part "Res2"))
    )
    (comp (ref "R63")
      (value "10K")
      (footprint "0603")
      (description "Resistor")
      (fields (field (name "PUBLISHER") "Altium Limited"))
      (libsource (lib "") (part "Res2_2"))
    )
    (comp (ref "R64")
      (value "10K")
      (footprint "0603")
      (description "Resistor")
      (fields (field (name "PUBLISHER") "Altium Limited"))
      (libsource (lib "Miscellaneous Devices") (part "Res2"))
    )
    (comp (ref "R65")
      (value "47K")
      (footprint "0603")
      (description "Resistor")
      (fields (field (name "PUBLISHER") "Altium Limited"))
      (libsource (lib "Miscellaneous Devices") (part "Res2"))
    )
    (comp (ref "R66")
      (value "4.7K")
      (footprint "0603")
      (description "Resistor")
      (fields (field (name "PUBLISHER") "Altium Limited"))
      (libsource (lib "Miscellaneous Devices") (part "Res2"))
    )
    (comp (ref "R67")
      (value "10K")
      (footprint "0603")
      (description "Resistor")
      (fields (field (name "PUBLISHER") "Altium Limited"))
      (libsource (lib "Miscellaneous Devices") (part "Res2"))
    )
    (comp (ref "R68")
      (value "4.7K")
      (footprint "0603")
      (description "Resistor")
      (fields (field (name "PUBLISHER") "Altium Limited"))
      (libsource (lib "Miscellaneous Devices") (part "Res2"))
    )
    (comp (ref "R69")
      (value "4K7")
      (footprint "0603")
      (description "Resistor")
      (fields (field (name "Comment") "Res2") (field (name "PUBLISHER") "Altium Limited"))
      (libsource (lib "") (part "Res2_1"))
    )
    (comp (ref "R70")
      (value "10K")
      (footprint "0603")
      (description "Resistor")
      (fields (field (name "Comment") "Res2") (field (name "PUBLISHER") "Altium Limited"))
      (libsource (lib "Miscellaneous Devices") (part "Res2"))
    )
    (comp (ref "R71")
      (value "470R")
      (footprint "0603")
      (description "Resistor")
      (fields (field (name "Comment") "Res2") (field (name "PUBLISHER") "Altium Limited"))
      (libsource (lib "") (part "Res2_3"))
    )
    (comp (ref "R72")
      (value "4.7K")
      (footprint "0603")
      (description "贴片电阻 0603")
      (fields (field (name "PUBLISHER") "Altium Limited"))
      (libsource (lib "") (part "Res2_3"))
    )
    (comp (ref "R73")
      (value "4.7K")
      (footprint "0603")
      (description "贴片电阻 0603")
      (fields (field (name "PUBLISHER") "Altium Limited"))
      (libsource (lib "") (part "Res2_3"))
    )
    (comp (ref "R74")
      (value "0Ω")
      (footprint "0805")
      (description "贴片电阻 0805 精度0.1%")
      (fields (field (name "Comment") "50R") (field (name "PUBLISHER") "Altium Limited"))
      (libsource (lib "") (part "Res2_2"))
    )
    (comp (ref "R75")
      (value "0Ω")
      (footprint "0805")
      (description "贴片电阻 0805 精度0.1%")
      (fields (field (name "Comment") "50R") (field (name "PUBLISHER") "Altium Limited"))
      (libsource (lib "") (part "Res2_2"))
    )
    (comp (ref "R76")
      (value "0Ω")
      (footprint "0805")
      (description "贴片电阻 0805 精度0.1%")
      (fields (field (name "Comment") "50R") (field (name "PUBLISHER") "Altium Limited"))
      (libsource (lib "") (part "Res2_2"))
    )
    (comp (ref "R77")
      (value "0Ω")
      (footprint "0805")
      (description "贴片电阻 0805 精度0.1%")
      (fields (field (name "Comment") "50R") (field (name "PUBLISHER") "Altium Limited"))
      (libsource (lib "") (part "Res2_2"))
    )
    (comp (ref "R78")
      (value "0Ω")
      (footprint "0805")
      (description "贴片电阻 0805 精度0.1%")
      (fields (field (name "Comment") "50R") (field (name "PUBLISHER") "Altium Limited"))
      (libsource (lib "") (part "Res2_2"))
    )
    (comp (ref "S1")
      (value "贴片拨码开关")
      (footprint "Switch10")
      (description "5P 2.54MM  黑色")
      (libsource (lib "User Schlib") (part "Switch"))
    )
    (comp (ref "U1")
      (value "LM2576HV-3.3V")
      (footprint "TO-263(S)")
      (description "贴片电源芯片 TO-263")
      (libsource (lib "LM2596") (part "Component_1"))
    )
    (comp (ref "U2")
      (value "AMS1117-1.8V")
      (footprint "SOT223")
      (description "VOLTAGE REGULATOR")
      (libsource (lib "userSCHLIB") (part "AS1117"))
    )
    (comp (ref "U3")
      (value "SN65HVD11")
      (footprint "SN65HVD11")
      (description "贴片芯片")
      (libsource (lib "User Library") (part "SN65HVD11"))
    )
    (comp (ref "U4")
      (value "SN65HVD11")
      (footprint "SN65HVD11")
      (description "贴片芯片")
      (libsource (lib "User Library") (part "SN65HVD11"))
    )
    (comp (ref "U6")
      (value "433M")
      (footprint "433M")
      (description "Header, 5-Pin, Dual row")
      (fields (field (name "PUBLISHER") "Altium Limited"))
      (libsource (lib "Miscellaneous Connectors") (part "Header 5X2A"))
    )
    (comp (ref "U7") (value "AT2659S") (footprint "SOT23-6") (libsource (lib "AT2659S") (part "Component_1")))
    (comp (ref "U8") (value "~") (footprint "PCBComponent_1") (libsource (lib "N20") (part "Component_1")))
    (comp (ref "Y1")
      (value "XTAL 8M")
      (footprint "XTAL 8M")
      (description "晶振")
      (libsource (lib "Schlib-user") (part "XTAL 8M"))
    )
    (comp (ref "Y2")
      (value "XTAL  32.768K")
      (footprint "R38")
      (description "晶振")
      (fields (field (name "PUBLISHER") "Altium Limited"))
      (libsource (lib "Miscellaneous Devices") (part "XTAL"))
    )
  )
  (nets
    (net (code "1") (name "/1P8") (class "Default")
      (node (ref "R54") (pin "1") (pinfunction "1_1") (pintype "passive"))
      (node (ref "R55") (pin "1") (pinfunction "1_1") (pintype "passive"))
      (node (ref "R56") (pin "1") (pinfunction "1_1") (pintype "passive"))
      (node (ref "R58") (pin "1") (pinfunction "1_1") (pintype "passive"))
      (node (ref "R59") (pin "1") (pinfunction "1_1") (pintype "passive"))
      (node (ref "R60") (pin "1") (pinfunction "1_1") (pintype "passive"))
      (node (ref "R66") (pin "1") (pinfunction "1_1") (pintype "passive"))
      (node (ref "R67") (pin "1") (pinfunction "1_1") (pintype "passive"))
      (node (ref "R68") (pin "1") (pinfunction "1_1") (pintype "passive"))
      (node (ref "U8") (pin "17") (pinfunction "VDDIO_1P8_17") (pintype "passive"))
    )
    (net (code "2") (name "/24VOUT") (class "Default")
      (node (ref "LED1") (pin "1") (pinfunction "A_1") (pintype "passive"))
      (node (ref "P2") (pin "1") (pinfunction "1_1") (pintype "passive"))
      (node (ref "P5") (pin "1") (pinfunction "1_1") (pintype "passive"))
      (node (ref "P6") (pin "1") (pinfunction "1_1") (pintype "passive"))
      (node (ref "Q3") (pin "1") (pinfunction "C_1") (pintype "passive"))
      (node (ref "Q8") (pin "1") (pinfunction "C_1") (pintype "passive"))
    )
    (net (code "3") (name "/ADC") (class "Default")
      (node (ref "P9") (pin "3") (pinfunction "3_3") (pintype "passive"))
    )
    (net (code "4") (name "/AIO2") (class "Default")
      (node (ref "P6") (pin "3") (pinfunction "3_3") (pintype "passive"))
      (node (ref "R26") (pin "2") (pinfunction "2_2") (pintype "passive"))
    )
    (net (code "5") (name "/AIO3") (class "Default")
      (node (ref "P7") (pin "3") (pinfunction "3_3") (pintype "passive"))
      (node (ref "R25") (pin "2") (pinfunction "2_2") (pintype "passive"))
    )
    (net (code "6") (name "/BIO2") (class "Default")
      (node (ref "P6") (pin "4") (pinfunction "4_4") (pintype "passive"))
      (node (ref "R21") (pin "2") (pinfunction "2_2") (pintype "passive"))
    )
    (net (code "7") (name "/BIO3") (class "Default")
      (node (ref "P7") (pin "4") (pinfunction "4_4") (pintype "passive"))
      (node (ref "R20") (pin "2") (pinfunction "2_2") (pintype "passive"))
    )
    (net (code "8") (name "/BOOT0") (class "Default")
      (node (ref "CPU1") (pin "94") (pinfunction "BOOT0_94") (pintype "input"))
      (node (ref "P12") (pin "2") (pinfunction "2_2") (pintype "passive"))
      (node (ref "R47") (pin "1") (pinfunction "1_1") (pintype "passive"))
    )
    (net (code "9") (name "/CTS") (class "Default")
      (node (ref "Q12") (pin "3") (pinfunction "C_3") (pintype "passive"))
      (node (ref "R59") (pin "2") (pinfunction "2_2") (pintype "passive"))
      (node (ref "U8") (pin "12") (pinfunction "UART0_CTS_12") (pintype "passive"))
    )
    (net (code "10") (name "/DATE1") (class "Default")
      (node (ref "P2") (pin "3") (pinfunction "3_3") (pintype "passive"))
      (node (ref "R74") (pin "1") (pinfunction "1_1") (pintype "passive"))
    )
    (net (code "11") (name "/DATE2") (class "Default")
      (node (ref "P2") (pin "4") (pinfunction "4_4") (pintype "passive"))
      (node (ref "R75") (pin "1") (pinfunction "1_1") (pintype "passive"))
    )
    (net (code "12") (name "/DATE3") (class "Default")
      (node (ref "P3") (pin "3") (pinfunction "3_3") (pintype "passive"))
      (node (ref "R76") (pin "1") (pinfunction "1_1") (pintype "passive"))
    )
    (net (code "13") (name "/DATE4") (class "Default")
      (node (ref "P4") (pin "3") (pinfunction "3_3") (pintype "passive"))
      (node (ref "R77") (pin "1") (pinfunction "1_1") (pintype "passive"))
    )
    (net (code "14") (name "/DATE5") (class "Default")
      (node (ref "P5") (pin "3") (pinfunction "3_3") (pintype "passive"))
      (node (ref "R78") (pin "1") (pinfunction "1_1") (pintype "passive"))
    )
    (net (code "15") (name "/DTR") (class "Default")
      (node (ref "Q16") (pin "3") (pinfunction "C_3") (pintype "passive"))
      (node (ref "R67") (pin "2") (pinfunction "2_2") (pintype "passive"))
      (node (ref "U8") (pin "15") (pinfunction "DTR_15") (pintype "passive"))
    )
    (net (code "16") (name "/EXT_GNSS") (class "Default")
      (node (ref "U8") (pin "56") (pinfunction "EXT_GNSS_LNA_EN_56") (pintype "passive"))
    )
    (net (code "17") (name "/GPIO0") (class "Default")
      (node (ref "P9") (pin "10") (pinfunction "10_10") (pintype "passive"))
    )
    (net (code "18") (name "/GPIO2") (class "Default")
      (node (ref "P9") (pin "12") (pinfunction "12_12") (pintype "passive"))
    )
    (net (code "19") (name "/GPIO4") (class "Default")
      (node (ref "P9") (pin "6") (pinfunction "6_6") (pintype "passive"))
    )
    (net (code "20") (name "/GPIO5") (class "Default")
      (node (ref "P9") (pin "8") (pinfunction "8_8") (pintype "passive"))
    )
    (net (code "21") (name "/GPIO12") (class "Default")
      (node (ref "P9") (pin "11") (pinfunction "11_11") (pintype "passive"))
    )
    (net (code "22") (name "/GPIO13") (class "Default")
      (node (ref "P9") (pin "13") (pinfunction "13_13") (pintype "passive"))
    )
    (net (code "23") (name "/GPIO14") (class "Default")
      (node (ref "P9") (pin "9") (pinfunction "9_9") (pintype "passive"))
    )
    (net (code "24") (name "/GPIO16") (class "Default")
      (node (ref "P9") (pin "7") (pinfunction "7_7") (pintype "passive"))
    )
    (net (code "25") (name "/InVCC") (class "Default")
      (node (ref "F1") (pin "2") (pinfunction "2_2") (pintype "passive"))
      (node (ref "P1") (pin "1") (pinfunction "1_1") (pintype "passive"))
    )
    (net (code "26") (name "/NETLIGHT") (class "Default")
      (node (ref "R49") (pin "1") (pinfunction "1_1") (pintype "passive"))
      (node (ref "U8") (pin "51") (pinfunction "NETLIGHT_51") (pintype "passive"))
    )
    (net (code "27") (name "/NRST") (class "Default")
      (node (ref "C26") (pin "2") (pinfunction "2_2") (pintype "passive"))
      (node (ref "CPU1") (pin "14") (pinfunction "NRST_14") (pintype "bidirectional"))
      (node (ref "P10") (pin "8") (pinfunction "8_8") (pintype "passive"))
      (node (ref "P13") (pin "8") (pinfunction "8_8") (pintype "passive"))
      (node (ref "R43") (pin "2") (pinfunction "2_2") (pintype "passive"))
    )
    (net (code "28") (name "/OSC32_IN") (class "Default")
      (node (ref "C24") (pin "2") (pinfunction "2_2") (pintype "passive"))
      (node (ref "CPU1") (pin "8") (pinfunction "PC14-OSC32_IN_8") (pintype "bidirectional"))
      (node (ref "Y2") (pin "1") (pinfunction "OSC1_1") (pintype "passive"))
    )
    (net (code "29") (name "/OSC32_OUT") (class "Default")
      (node (ref "C25") (pin "2") (pinfunction "2_2") (pintype "passive"))
      (node (ref "CPU1") (pin "9") (pinfunction "PC15-OSC32_OUT_9") (pintype "bidirectional"))
      (node (ref "Y2") (pin "2") (pinfunction "OSC2_2") (pintype "passive"))
    )
    (net (code "30") (name "/OSC_IN") (class "Default")
      (node (ref "C16") (pin "2") (pinfunction "2_2") (pintype "passive"))
      (node (ref "CPU1") (pin "12") (pinfunction "OSC_IN_12") (pintype "input"))
      (node (ref "Y1") (pin "1") (pinfunction "OSC1_1") (pintype "passive"))
    )
    (net (code "31") (name "/OSC_OUT") (class "Default")
      (node (ref "C17") (pin "2") (pinfunction "2_2") (pintype "passive"))
      (node (ref "CPU1") (pin "13") (pinfunction "OSC_OUT_13") (pintype "output"))
      (node (ref "Y1") (pin "2") (pinfunction "OSC2_2") (pintype "passive"))
    )
    (net (code "32") (name "/PA0") (class "Default")
      (node (ref "CPU1") (pin "23") (pinfunction "PA0-WKUP_23") (pintype "bidirectional"))
      (node (ref "P14") (pin "3") (pinfunction "3_3") (pintype "passive"))
    )
    (net (code "33") (name "/PA1") (class "Default")
      (node (ref "CPU1") (pin "24") (pinfunction "PA1_24") (pintype "bidirectional"))
      (node (ref "R11") (pin "2") (pinfunction "2_2") (pintype "passive"))
      (node (ref "R77") (pin "2") (pinfunction "2_2") (pintype "passive"))
    )
    (net (code "34") (name "/PA2") (class "Default")
      (node (ref "CPU1") (pin "25") (pinfunction "PA2_25") (pintype "bidirectional"))
      (node (ref "R78") (pin "2") (pinfunction "2_2") (pintype "passive"))
      (node (ref "R9") (pin "2") (pinfunction "2_2") (pintype "passive"))
    )
    (net (code "35") (name "/PA3") (class "Default")
      (node (ref "CPU1") (pin "26") (pinfunction "PA3_26") (pintype "bidirectional"))
    )
    (net (code "36") (name "/PA4") (class "Default")
      (node (ref "CPU1") (pin "29") (pinfunction "PA4_29") (pintype "bidirectional"))
      (node (ref "U6") (pin "1") (pinfunction "1_1") (pintype "passive"))
    )
    (net (code "37") (name "/PA5") (class "Default")
      (node (ref "CPU1") (pin "30") (pinfunction "PA5_30") (pintype "bidirectional"))
      (node (ref "U6") (pin "4") (pinfunction "4_4") (pintype "passive"))
    )
    (net (code "38") (name "/PA6") (class "Default")
      (node (ref "CPU1") (pin "31") (pinfunction "PA6_31") (pintype "bidirectional"))
      (node (ref "U6") (pin "3") (pinfunction "3_3") (pintype "passive"))
    )
    (net (code "39") (name "/PA7") (class "Default")
      (node (ref "CPU1") (pin "32") (pinfunction "PA7_32") (pintype "bidirectional"))
      (node (ref "U6") (pin "2") (pinfunction "2_2") (pintype "passive"))
    )
    (net (code "40") (name "/PA8") (class "Default")
      (node (ref "CPU1") (pin "67") (pinfunction "PA8_67") (pintype "bidirectional"))
    )
    (net (code "41") (name "/PA9") (class "Default")
      (node (ref "CPU1") (pin "68") (pinfunction "PA9_68") (pintype "bidirectional"))
      (node (ref "P11") (pin "3") (pinfunction "3_3") (pintype "passive"))
    )
    (net (code "42") (name "/PA10") (class "Default")
      (node (ref "CPU1") (pin "69") (pinfunction "PA10_69") (pintype "bidirectional"))
      (node (ref "P11") (pin "2") (pinfunction "2_2") (pintype "passive"))
    )
    (net (code "43") (name "/PA11") (class "Default")
      (node (ref "CPU1") (pin "70") (pinfunction "PA11_70") (pintype "bidirectional"))
      (node (ref "P8") (pin "3") (pinfunction "3_3") (pintype "passive"))
    )
    (net (code "44") (name "/PA12") (class "Default")
      (node (ref "CPU1") (pin "71") (pinfunction "PA12_71") (pintype "bidirectional"))
      (node (ref "P8") (pin "2") (pinfunction "2_2") (pintype "passive"))
    )
    (net (code "45") (name "/PB0") (class "Default")
      (node (ref "CPU1") (pin "35") (pinfunction "PB0_35") (pintype "bidirectional"))
    )
    (net (code "46") (name "/PB1") (class "Default")
      (node (ref "CPU1") (pin "36") (pinfunction "PB1_36") (pintype "bidirectional"))
    )
    (net (code "47") (name "/PB5") (class "Default")
      (node (ref "CPU1") (pin "91") (pinfunction "PB5_91") (pintype "bidirectional"))
    )
    (net (code "48") (name "/PB6") (class "Default")
      (node (ref "CPU1") (pin "92") (pinfunction "PB6_92") (pintype "bidirectional"))
      (node (ref "U6") (pin "7") (pinfunction "7_7") (pintype "passive"))
    )
    (net (code "49") (name "/PB7") (class "Default")
      (node (ref "CPU1") (pin "93") (pinfunction "PB7_93") (pintype "bidirectional"))
      (node (ref "U6") (pin "8") (pinfunction "8_8") (pintype "passive"))
    )
    (net (code "50") (name "/PB8") (class "Default")
      (node (ref "CPU1") (pin "95") (pinfunction "PB8_95") (pintype "bidirectional"))
      (node (ref "U3") (pin "2") (pinfunction "RE_2") (pintype "passive"))
      (node (ref "U3") (pin "3") (pinfunction "DE_3") (pintype "passive"))
    )
    (net (code "51") (name "/PB9") (class "Default")
      (node (ref "CPU1") (pin "96") (pinfunction "PB9_96") (pintype "bidirectional"))
      (node (ref "U4") (pin "2") (pinfunction "RE_2") (pintype "passive"))
      (node (ref "U4") (pin "3") (pinfunction "DE_3") (pintype "passive"))
    )
    (net (code "52") (name "/PB10") (class "Default")
      (node (ref "CPU1") (pin "47") (pinfunction "PB10_47") (pintype "bidirectional"))
    )
    (net (code "53") (name "/PB11") (class "Default")
      (node (ref "CPU1") (pin "48") (pinfunction "PB11_48") (pintype "bidirectional"))
      (node (ref "P13") (pin "9") (pinfunction "9_9") (pintype "passive"))
    )
    (net (code "54") (name "/PB12") (class "Default")
      (node (ref "CPU1") (pin "51") (pinfunction "PB12_51") (pintype "bidirectional"))
      (node (ref "P13") (pin "4") (pinfunction "4_4") (pintype "passive"))
    )
    (net (code "55") (name "/PB13") (class "Default")
      (node (ref "CPU1") (pin "52") (pinfunction "PB13_52") (pintype "bidirectional"))
      (node (ref "P13") (pin "5") (pinfunction "5_5") (pintype "passive"))
    )
    (net (code "56") (name "/PB14") (class "Default")
      (node (ref "CPU1") (pin "53") (pinfunction "PB14_53") (pintype "bidirectional"))
      (node (ref "P13") (pin "2") (pinfunction "2_2") (pintype "passive"))
    )
    (net (code "57") (name "/PB15") (class "Default")
      (node (ref "CPU1") (pin "54") (pinfunction "PB15_54") (pintype "bidirectional"))
      (node (ref "P13") (pin "3") (pinfunction "3_3") (pintype "passive"))
    )
    (net (code "58") (name "/PC0") (class "Default")
      (node (ref "CPU1") (pin "15") (pinfunction "PC0_15") (pintype "bidirectional"))
      (node (ref "R10") (pin "2") (pinfunction "2_2") (pintype "passive"))
      (node (ref "R76") (pin "2") (pinfunction "2_2") (pintype "passive"))
    )
    (net (code "59") (name "/PC1") (class "Default")
      (node (ref "CPU1") (pin "16") (pinfunction "PC1_16") (pintype "bidirectional"))
      (node (ref "R75") (pin "2") (pinfunction "2_2") (pintype "passive"))
      (node (ref "R8") (pin "2") (pinfunction "2_2") (pintype "passive"))
    )
    (net (code "60") (name "/PC2") (class "Default")
      (node (ref "CPU1") (pin "17") (pinfunction "PC2_17") (pintype "bidirectional"))
      (node (ref "R7") (pin "2") (pinfunction "2_2") (pintype "passive"))
      (node (ref "R74") (pin "2") (pinfunction "2_2") (pintype "passive"))
    )
    (net (code "61") (name "/PC3") (class "Default")
      (node (ref "CPU1") (pin "18") (pinfunction "PC3_18") (pintype "bidirectional"))
      (node (ref "P3") (pin "4") (pinfunction "4_4") (pintype "passive"))
      (node (ref "P4") (pin "4") (pinfunction "4_4") (pintype "passive"))
      (node (ref "P5") (pin "4") (pinfunction "4_4") (pintype "passive"))
    )
    (net (code "62") (name "/PC4") (class "Default")
      (node (ref "CPU1") (pin "33") (pinfunction "PC4_33") (pintype "bidirectional"))
      (node (ref "U6") (pin "5") (pinfunction "5_5") (pintype "passive"))
    )
    (net (code "63") (name "/PC5") (class "Default")
      (node (ref "CPU1") (pin "34") (pinfunction "PC5_34") (pintype "bidirectional"))
    )
    (net (code "64") (name "/PC6") (class "Default")
      (node (ref "CPU1") (pin "63") (pinfunction "PC6_63") (pintype "bidirectional"))
    )
    (net (code "65") (name "/PC7") (class "Default")
      (node (ref "CPU1") (pin "64") (pinfunction "PC7_64") (pintype "bidirectional"))
    )
    (net (code "66") (name "/PC8") (class "Default")
      (node (ref "CPU1") (pin "65") (pinfunction "PC8_65") (pintype "bidirectional"))
    )
    (net (code "67") (name "/PC9") (class "Default")
      (node (ref "CPU1") (pin "66") (pinfunction "PC9_66") (pintype "bidirectional"))
    )
    (net (code "68") (name "/PC10") (class "Default")
      (node (ref "CPU1") (pin "78") (pinfunction "PC10_78") (pintype "bidirectional"))
      (node (ref "U4") (pin "4") (pinfunction "D_4") (pintype "passive"))
    )
    (net (code "69") (name "/PC11") (class "Default")
      (node (ref "CPU1") (pin "79") (pinfunction "PC11_79") (pintype "bidirectional"))
      (node (ref "U4") (pin "1") (pinfunction "R_1") (pintype "passive"))
    )
    (net (code "70") (name "/PC12") (class "Default")
      (node (ref "CPU1") (pin "80") (pinfunction "PC12_80") (pintype "bidirectional"))
      (node (ref "U3") (pin "4") (pinfunction "D_4") (pintype "passive"))
    )
    (net (code "71") (name "/PC13") (class "Default")
      (node (ref "CPU1") (pin "7") (pinfunction "PC13-TAMPER-RTC_7") (pintype "bidirectional"))
    )
    (net (code "72") (name "/PD0") (class "Default")
      (node (ref "CPU1") (pin "81") (pinfunction "PD0_81") (pintype "bidirectional"))
      (node (ref "P9") (pin "1") (pinfunction "1_1") (pintype "passive"))
    )
    (net (code "73") (name "/PD1") (class "Default")
      (node (ref "CPU1") (pin "82") (pinfunction "PD1_82") (pintype "bidirectional"))
    )
    (net (code "74") (name "/PD2") (class "Default")
      (node (ref "CPU1") (pin "83") (pinfunction "PD2_83") (pintype "bidirectional"))
      (node (ref "U3") (pin "1") (pinfunction "R_1") (pintype "passive"))
    )
    (net (code "75") (name "/PD3") (class "Default")
      (node (ref "CPU1") (pin "84") (pinfunction "PD3_84") (pintype "bidirectional"))
      (node (ref "Q11") (pin "3") (pinfunction "C_3") (pintype "passive"))
      (node (ref "R57") (pin "2") (pinfunction "2_2") (pintype "passive"))
    )
    (net (code "76") (name "/PD4") (class "Default")
      (node (ref "CPU1") (pin "85") (pinfunction "PD4_85") (pintype "bidirectional"))
      (node (ref "Q12") (pin "2") (pinfunction "E_2") (pintype "passive"))
    )
    (net (code "77") (name "/PD5") (class "Default")
      (node (ref "CPU1") (pin "86") (pinfunction "PD5_86") (pintype "bidirectional"))
      (node (ref "P9") (pin "4") (pinfunction "4_4") (pintype "passive"))
      (node (ref "Q10") (pin "2") (pinfunction "E_2") (pintype "passive"))
      (node (ref "R24") (pin "2") (pinfunction "2_2") (pintype "passive"))
    )
    (net (code "78") (name "/PD6") (class "Default")
      (node (ref "CPU1") (pin "87") (pinfunction "PD6_87") (pintype "bidirectional"))
      (node (ref "P9") (pin "2") (pinfunction "2_2") (pintype "passive"))
      (node (ref "Q9") (pin "3") (pinfunction "C_3") (pintype "passive"))
      (node (ref "R23") (pin "2") (pinfunction "2_2") (pintype "passive"))
      (node (ref "R53") (pin "2") (pinfunction "2_2") (pintype "passive"))
    )
    (net (code "79") (name "/PD7") (class "Default")
      (node (ref "CPU1") (pin "88") (pinfunction "PD7_88") (pintype "bidirectional"))
      (node (ref "P9") (pin "5") (pinfunction "5_5") (pintype "passive"))
    )
    (net (code "80") (name "/PD8") (class "Default")
      (node (ref "CPU1") (pin "55") (pinfunction "PD8_55") (pintype "bidirectional"))
      (node (ref "P1") (pin "3") (pinfunction "3_3") (pintype "passive"))
    )
    (net (code "81") (name "/PD9") (class "Default")
      (node (ref "CPU1") (pin "56") (pinfunction "PD9_56") (pintype "bidirectional"))
      (node (ref "P1") (pin "4") (pinfunction "4_4") (pintype "passive"))
    )
    (net (code "82") (name "/PD10") (class "Default")
      (node (ref "CPU1") (pin "57") (pinfunction "PD10_57") (pintype "bidirectional"))
      (node (ref "P1") (pin "5") (pinfunction "5_5") (pintype "passive"))
    )
    (net (code "83") (name "/PD11") (class "Default")
      (node (ref "CPU1") (pin "58") (pinfunction "PD11_58") (pintype "bidirectional"))
      (node (ref "Q16") (pin "2") (pinfunction "E_2") (pintype "passive"))
    )
    (net (code "84") (name "/PE0") (class "Default")
      (node (ref "CPU1") (pin "97") (pinfunction "PE0_97") (pintype "bidirectional"))
      (node (ref "D12") (pin "2") (pinfunction "K_2") (pintype "passive"))
    )
    (net (code "85") (name "/PE1") (class "Default")
      (node (ref "CPU1") (pin "98") (pinfunction "PE1_98") (pintype "bidirectional"))
    )
    (net (code "86") (name "/PE2") (class "Default")
      (node (ref "CPU1") (pin "1") (pinfunction "PE2_1") (pintype "bidirectional"))
      (node (ref "S1") (pin "10") (pinfunction "10_10") (pintype "passive"))
    )
    (net (code "87") (name "/PE3") (class "Default")
      (node (ref "CPU1") (pin "2") (pinfunction "PE3_2") (pintype "bidirectional"))
      (node (ref "S1") (pin "9") (pinfunction "9_9") (pintype "passive"))
    )
    (net (code "88") (name "/PE4") (class "Default")
      (node (ref "CPU1") (pin "3") (pinfunction "PE4_3") (pintype "bidirectional"))
      (node (ref "S1") (pin "8") (pinfunction "8_8") (pintype "passive"))
    )
    (net (code "89") (name "/PE5") (class "Default")
      (node (ref "CPU1") (pin "4") (pinfunction "PE5_4") (pintype "bidirectional"))
      (node (ref "S1") (pin "7") (pinfunction "7_7") (pintype "passive"))
    )
    (net (code "90") (name "/PE6") (class "Default")
      (node (ref "CPU1") (pin "5") (pinfunction "PE6_5") (pintype "bidirectional"))
      (node (ref "S1") (pin "6") (pinfunction "6_6") (pintype "passive"))
    )
    (net (code "91") (name "/PE7") (class "Default")
      (node (ref "CPU1") (pin "38") (pinfunction "PE7_38") (pintype "bidirectional"))
      (node (ref "D14") (pin "1") (pinfunction "A_1") (pintype "passive"))
    )
    (net (code "92") (name "/PE8") (class "Default")
      (node (ref "CPU1") (pin "39") (pinfunction "PE8_39") (pintype "bidirectional"))
    )
    (net (code "93") (name "/PE9") (class "Default")
      (node (ref "CPU1") (pin "40") (pinfunction "PE9_40") (pintype "bidirectional"))
    )
    (net (code "94") (name "/PE10") (class "Default")
      (node (ref "CPU1") (pin "41") (pinfunction "PE10_41") (pintype "bidirectional"))
    )
    (net (code "95") (name "/PE11") (class "Default")
      (node (ref "CPU1") (pin "42") (pinfunction "PE11_42") (pintype "bidirectional"))
    )
    (net (code "96") (name "/PE12") (class "Default")
      (node (ref "CPU1") (pin "43") (pinfunction "PE12_43") (pintype "bidirectional"))
    )
    (net (code "97") (name "/PE13") (class "Default")
      (node (ref "CPU1") (pin "44") (pinfunction "PE13_44") (pintype "bidirectional"))
    )
    (net (code "98") (name "/PE14") (class "Default")
      (node (ref "CPU1") (pin "45") (pinfunction "PE14_45") (pintype "bidirectional"))
      (node (ref "P8") (pin "4") (pinfunction "4_4") (pintype "passive"))
    )
    (net (code "99") (name "/PE15") (class "Default")
      (node (ref "CPU1") (pin "46") (pinfunction "PE15_46") (pintype "bidirectional"))
      (node (ref "P8") (pin "5") (pinfunction "5_5") (pintype "passive"))
    )
    (net (code "100") (name "/POW_ON") (class "Default")
      (node (ref "CPU1") (pin "59") (pinfunction "PD12_59") (pintype "bidirectional"))
      (node (ref "R42") (pin "2") (pinfunction "2_2") (pintype "passive"))
      (node (ref "R63") (pin "2") (pinfunction "2_2") (pintype "passive"))
    )
    (net (code "101") (name "/PWRKEY") (class "Default")
      (node (ref "Q14") (pin "3") (pinfunction "C_3") (pintype "passive"))
      (node (ref "U8") (pin "14") (pinfunction "PWRKEY_14") (pintype "passive"))
    )
    (net (code "102") (name "/RESET") (class "Default")
      (node (ref "Q15") (pin "3") (pinfunction "C_3") (pintype "passive"))
      (node (ref "U8") (pin "13") (pinfunction "RESET_N_13") (pintype "passive"))
    )
    (net (code "103") (name "/RESET_CTL") (class "Default")
      (node (ref "CPU1") (pin "60") (pinfunction "PD13_60") (pintype "bidirectional"))
      (node (ref "Q15") (pin "2") (pinfunction "E_2") (pintype "passive"))
      (node (ref "R65") (pin "2") (pinfunction "2_2") (pintype "passive"))
    )
    (net (code "104") (name "/RF_GNSS") (class "Default")
      (node (ref "U7") (pin "6") (pinfunction "RFOUT_6") (pintype "passive"))
      (node (ref "U8") (pin "54") (pinfunction "RF_ANT_GNSS_54") (pintype "passive"))
    )
    (net (code "105") (name "/RF_MAIN") (class "Default")
      (node (ref "C29") (pin "2") (pinfunction "2_2") (pintype "passive"))
      (node (ref "R52") (pin "1") (pinfunction "1_1") (pintype "passive"))
    )
    (net (code "106") (name "/RING") (class "Default")
      (node (ref "R69") (pin "1") (pinfunction "1_1") (pintype "passive"))
      (node (ref "U8") (pin "50") (pinfunction "RING_50") (pintype "passive"))
    )
    (net (code "107") (name "/RTS") (class "Default")
      (node (ref "Q11") (pin "2") (pinfunction "E_2") (pintype "passive"))
      (node (ref "U8") (pin "11") (pinfunction "UART0_RTS_11") (pintype "passive"))
    )
    (net (code "109") (name "/RXD") (class "Default")
      (node (ref "Q10") (pin "3") (pinfunction "C_3") (pintype "passive"))
      (node (ref "R55") (pin "2") (pinfunction "2_2") (pintype "passive"))
      (node (ref "U8") (pin "10") (pinfunction "UART0_RX_10") (pintype "passive"))
    )
    (net (code "110") (name "/SWCLK") (class "Default")
      (node (ref "CPU1") (pin "76") (pinfunction "PA14/JTCK/SWCLK_76") (pintype "bidirectional"))
      (node (ref "P10") (pin "7") (pinfunction "7_7") (pintype "passive"))
    )
    (net (code "111") (name "/SWDIO") (class "Default")
      (node (ref "CPU1") (pin "72") (pinfunction "PA13/JTMS/SWDIO_72") (pintype "bidirectional"))
      (node (ref "P10") (pin "2") (pinfunction "2_2") (pintype "passive"))
    )
    (net (code "112") (name "/TDI") (class "Default")
      (node (ref "CPU1") (pin "77") (pinfunction "PA15/JTDI_77") (pintype "bidirectional"))
    )
    (net (code "113") (name "/TDO") (class "Default")
      (node (ref "CPU1") (pin "89") (pinfunction "PB3/JTDO_89") (pintype "bidirectional"))
    )
    (net (code "114") (name "/TERM_ON_CTL") (class "Default")
      (node (ref "CPU1") (pin "61") (pinfunction "PD14_61") (pintype "bidirectional"))
    )
    (net (code "116") (name "/TXD") (class "Default")
      (node (ref "Q9") (pin "2") (pinfunction "E_2") (pintype "passive"))
      (node (ref "U8") (pin "9") (pinfunction "UART0_TX_9") (pintype "passive"))
    )
    (net (code "117") (name "/UIM_CLK") (class "Default")
      (node (ref "R44") (pin "2") (pinfunction "2_2") (pintype "passive"))
      (node (ref "U8") (pin "31") (pinfunction "UIM_CLK_31") (pintype "passive"))
    )
    (net (code "118") (name "/UIM_DATA") (class "Default")
      (node (ref "R46") (pin "2") (pinfunction "2_2") (pintype "passive"))
      (node (ref "U8") (pin "30") (pinfunction "UIM_DATA_30") (pintype "passive"))
    )
    (net (code "119") (name "/UIM_PRESENT") (class "Default")
      (node (ref "U8") (pin "33") (pinfunction "UIM_PRESENT_33") (pintype "passive"))
    )
    (net (code "120") (name "/UIM_RESET") (class "Default")
      (node (ref "R45") (pin "2") (pinfunction "2_2") (pintype "passive"))
      (node (ref "U8") (pin "32") (pinfunction "UIM_RESET_32") (pintype "passive"))
    )
    (net (code "121") (name "/VUIM") (class "Default")
      (node (ref "C18") (pin "2") (pinfunction "2_2") (pintype "passive"))
      (node (ref "Card1") (pin "1") (pinfunction "VCC_1") (pintype "power_in"))
      (node (ref "D16") (pin "3") (pintype "passive"))
      (node (ref "R48") (pin "2") (pinfunction "2_2") (pintype "passive"))
      (node (ref "U8") (pin "29") (pinfunction "VUIM_29") (pintype "passive"))
    )
    (net (code "122") (name "/WAKEUP_CTL") (class "Default")
      (node (ref "CPU1") (pin "62") (pinfunction "PD15_62") (pintype "bidirectional"))
    )
    (net (code "123") (name "/nTRST") (class "Default")
      (node (ref "CPU1") (pin "90") (pinfunction "PB4/JNTRST_90") (pintype "bidirectional"))
    )
    (net (code "124") (name "1.8V") (class "Default")
      (node (ref "C6") (pin "2") (pinfunction "2_2") (pintype "passive"))
      (node (ref "C7") (pin "1") (pinfunction "1_1") (pintype "passive"))
      (node (ref "D1") (pin "2") (pinfunction "2_2") (pintype "passive"))
      (node (ref "U2") (pin "2") (pinfunction "Vout_2") (pintype "passive"))
      (node (ref "U2") (pin "4") (pinfunction "Vout_4") (pintype "passive"))
    )
    (net (code "125") (name "24V+") (class "Default")
      (node (ref "C1") (pin "1") (pinfunction "1_1") (pintype "passive"))
      (node (ref "C2") (pin "2") (pinfunction "2_2") (pintype "passive"))
      (node (ref "D2") (pin "2") (pinfunction "K_2") (pintype "passive"))
      (node (ref "P7") (pin "1") (pinfunction "1_1") (pintype "passive"))
      (node (ref "P8") (pin "1") (pinfunction "1_1") (pintype "passive"))
      (node (ref "Q3") (pin "3") (pinfunction "E_3") (pintype "passive"))
      (node (ref "Q8") (pin "3") (pinfunction "E_3") (pintype "passive"))
      (node (ref "R28") (pin "1") (pinfunction "1_1") (pintype "passive"))
      (node (ref "R32") (pin "1") (pinfunction "1_1") (pintype "passive"))
      (node (ref "U1") (pin "1") (pinfunction "VIN_1") (pintype "passive"))
    )
    (net (code "126") (name "DGND") (class "Default")
      (node (ref "R12") (pin "2") (pinfunction "2_2") (pintype "passive"))
      (node (ref "R19") (pin "2") (pinfunction "2_2") (pintype "passive"))
    )
    (net (code "127") (name "GND") (class "Default")
      (node (ref "C1") (pin "2") (pinfunction "2_2") (pintype "passive"))
      (node (ref "C10") (pin "1") (pinfunction "1_1") (pintype "passive"))
      (node (ref "C11") (pin "1") (pinfunction "1_1") (pintype "passive"))
      (node (ref "C12") (pin "1") (pinfunction "1_1") (pintype "passive"))
      (node (ref "C16") (pin "1") (pinfunction "1_1") (pintype "passive"))
      (node (ref "C17") (pin "1") (pinfunction "1_1") (pintype "passive"))
      (node (ref "C18") (pin "1") (pinfunction "1_1") (pintype "passive"))
      (node (ref "C19") (pin "2") (pinfunction "2_2") (pintype "passive"))
      (node (ref "C2") (pin "1") (pinfunction "1_1") (pintype "passive"))
      (node (ref "C20") (pin "1") (pinfunction "1_1") (pintype "passive"))
      (node (ref "C21") (pin "1") (pinfunction "1_1") (pintype "passive"))
      (node (ref "C22") (pin "1") (pinfunction "1_1") (pintype "passive"))
      (node (ref "C23") (pin "1") (pinfunction "1_1") (pintype "passive"))
      (node (ref "C24") (pin "1") (pinfunction "1_1") (pintype "passive"))
      (node (ref "C25") (pin "1") (pinfunction "1_1") (pintype "passive"))
      (node (ref "C26") (pin "1") (pinfunction "1_1") (pintype "passive"))
      (node (ref "C28") (pin "1") (pinfunction "1_1") (pintype "passive"))
      (node (ref "C29") (pin "1") (pinfunction "1_1") (pintype "passive"))
      (node (ref "C3") (pin "1") (pinfunction "1_1") (pintype "passive"))
      (node (ref "C30") (pin "1") (pinfunction "1_1") (pintype "passive"))
      (node (ref "C31") (pin "1") (pinfunction "1_1") (pintype "passive"))
      (node (ref "C32") (pin "1") (pinfunction "1_1") (pintype "passive"))
      (node (ref "C4") (pin "2") (pinfunction "2_2") (pintype "passive"))
      (node (ref "C5") (pin "1") (pinfunction "1_1") (pintype "passive"))
      (node (ref "C6") (pin "1") (pinfunction "1_1") (pintype "passive"))
      (node (ref "C7") (pin "2") (pinfunction "2_2") (pintype "passive"))
      (node (ref "C8") (pin "2") (pinfunction "2_2") (pintype "passive"))
      (node (ref "C9") (pin "1") (pinfunction "1_1") (pintype "passive"))
      (node (ref "CPU1") (pin "10") (pinfunction "VSS_5_10") (pintype "power_in"))
      (node (ref "CPU1") (pin "19") (pinfunction "VSSA_19") (pintype "power_in"))
      (node (ref "CPU1") (pin "20") (pinfunction "VREF-_20") (pintype "power_in"))
      (node (ref "CPU1") (pin "27") (pinfunction "VSS_4_27") (pintype "power_in"))
      (node (ref "CPU1") (pin "37") (pinfunction "PB2/BOOT1_37") (pintype "bidirectional"))
      (node (ref "CPU1") (pin "49") (pinfunction "VSS_1_49") (pintype "power_in"))
      (node (ref "CPU1") (pin "74") (pinfunction "VSS_2_74") (pintype "power_in"))
      (node (ref "CPU1") (pin "99") (pinfunction "VSS_3_99") (pintype "power_in"))
      (node (ref "D11") (pin "2") (pinfunction "K_2") (pintype "passive"))
      (node (ref "D16") (pin "2") (pintype "passive"))
      (node (ref "D4") (pin "1") (pinfunction "A_1") (pintype "passive"))
      (node (ref "D5") (pin "1") (pinfunction "A_1") (pintype "passive"))
      (node (ref "D6") (pin "1") (pinfunction "A_1") (pintype "passive"))
      (node (ref "D8") (pin "1") (pinfunction "A_1") (pintype "passive"))
      (node (ref "D9") (pin "1") (pinfunction "A_1") (pintype "passive"))
      (node (ref "P1") (pin "2") (pinfunction "2_2") (pintype "passive"))
      (node (ref "P10") (pin "1") (pinfunction "1_1") (pintype "passive"))
      (node (ref "P11") (pin "4") (pinfunction "4_4") (pintype "passive"))
      (node (ref "P13") (pin "7") (pinfunction "7_7") (pintype "passive"))
      (node (ref "P14") (pin "2") (pinfunction "2_2") (pintype "passive"))
      (node (ref "P2") (pin "2") (pinfunction "2_2") (pintype "passive"))
      (node (ref "P3") (pin "2") (pinfunction "2_2") (pintype "passive"))
      (node (ref "P4") (pin "2") (pinfunction "2_2") (pintype "passive"))
      (node (ref "P5") (pin "2") (pinfunction "2_2") (pintype "passive"))
      (node (ref "P6") (pin "2") (pinfunction "2_2") (pintype "passive"))
      (node (ref "P7") (pin "2") (pinfunction "2_2") (pintype "passive"))
      (node (ref "P8") (pin "6") (pinfunction "6_6") (pintype "passive"))
      (node (ref "P9") (pin "14") (pinfunction "14_14") (pintype "passive"))
      (node (ref "P9") (pin "16") (pinfunction "16_16") (pintype "passive"))
      (node (ref "Q14") (pin "2") (pinfunction "E_2") (pintype "passive"))
      (node (ref "Q17") (pin "2") (pinfunction "E_2") (pintype "passive"))
      (node (ref "Q4") (pin "2") (pinfunction "E_2") (pintype "passive"))
      (node (ref "Q5") (pin "1") (pinfunction "E_1") (pintype "passive"))
      (node (ref "Q7") (pin "2") (pinfunction "E_2") (pintype "passive"))
      (node (ref "R13") (pin "2") (pinfunction "2_2") (pintype "passive"))
      (node (ref "R14") (pin "1") (pinfunction "1_1") (pintype "passive"))
      (node (ref "R15") (pin "2") (pinfunction "2_2") (pintype "passive"))
      (node (ref "R16") (pin "2") (pinfunction "2_2") (pintype "passive"))
      (node (ref "R17") (pin "2") (pinfunction "2_2") (pintype "passive"))
      (node (ref "R18") (pin "2") (pinfunction "2_2") (pintype "passive"))
      (node (ref "R19") (pin "1") (pinfunction "1_1") (pintype "passive"))
      (node (ref "R3") (pin "2") (pinfunction "2_2") (pintype "passive"))
      (node (ref "R38") (pin "1") (pinfunction "1_1") (pintype "passive"))
      (node (ref "R39") (pin "1") (pinfunction "1_1") (pintype "passive"))
      (node (ref "R41") (pin "2") (pinfunction "2_2") (pintype "passive"))
      (node (ref "R47") (pin "2") (pinfunction "2_2") (pintype "passive"))
      (node (ref "R50") (pin "2") (pinfunction "2_2") (pintype "passive"))
      (node (ref "R64") (pin "1") (pinfunction "1_1") (pintype "passive"))
      (node (ref "R70") (pin "2") (pinfunction "2_2") (pintype "passive"))
      (node (ref "R73") (pin "1") (pinfunction "1_1") (pintype "passive"))
      (node (ref "S1") (pin "1") (pinfunction "1_1") (pintype "passive"))
      (node (ref "S1") (pin "2") (pinfunction "2_2") (pintype "passive"))
      (node (ref "S1") (pin "3") (pinfunction "3_3") (pintype "passive"))
      (node (ref "S1") (pin "4") (pinfunction "4_4") (pintype "passive"))
      (node (ref "S1") (pin "5") (pinfunction "5_5") (pintype "passive"))
      (node (ref "U1") (pin "3") (pinfunction "GND_3") (pintype "passive"))
      (node (ref "U1") (pin "5") (pinfunction "~{ON}_5") (pintype "passive"))
      (node (ref "U2") (pin "1") (pinfunction "GND_1") (pintype "passive"))
      (node (ref "U3") (pin "5") (pinfunction "GND_5") (pintype "passive"))
      (node (ref "U4") (pin "5") (pinfunction "GND_5") (pintype "passive"))
      (node (ref "U6") (pin "9") (pinfunction "9_9") (pintype "passive"))
      (node (ref "U7") (pin "1") (pinfunction "GND_1") (pintype "passive"))
      (node (ref "U7") (pin "2") (pinfunction "GND_2") (pintype "passive"))
      (node (ref "U8") (pin "1") (pinfunction "GND_1") (pintype "passive"))
      (node (ref "U8") (pin "18") (pinfunction "GND_18") (pintype "passive"))
      (node (ref "U8") (pin "19") (pinfunction "GND_19") (pintype "passive"))
      (node (ref "U8") (pin "23") (pinfunction "GND_23") (pintype "passive"))
      (node (ref "U8") (pin "24") (pinfunction "GND_24") (pintype "passive"))
      (node (ref "U8") (pin "34") (pinfunction "GND_34") (pintype "passive"))
      (node (ref "U8") (pin "35") (pinfunction "GND_35") (pintype "passive"))
      (node (ref "U8") (pin "4") (pinfunction "GND_4") (pintype "passive"))
      (node (ref "U8") (pin "42") (pinfunction "GND_42") (pintype "passive"))
      (node (ref "U8") (pin "52") (pinfunction "GND_52") (pintype "passive"))
      (node (ref "U8") (pin "53") (pinfunction "GND_53") (pintype "passive"))
      (node (ref "U8") (pin "55") (pinfunction "GND_55") (pintype "passive"))
      (node (ref "U8") (pin "57") (pinfunction "GND_57") (pintype "passive"))
      (node (ref "U8") (pin "66") (pinfunction "GND_66") (pintype "passive"))
      (node (ref "U8") (pin "68") (pinfunction "GND_68") (pintype "passive"))
    )
    (net (code "128") (name "Net-(C8-Pad1)") (class "Default")
      (node (ref "C8") (pin "1") (pinfunction "1_1") (pintype "passive"))
      (node (ref "R14") (pin "2") (pinfunction "2_2") (pintype "passive"))
      (node (ref "R7") (pin "1") (pinfunction "1_1") (pintype "passive"))
    )
    (net (code "129") (name "Net-(C9-Pad2)") (class "Default")
      (node (ref "C9") (pin "2") (pinfunction "2_2") (pintype "passive"))
      (node (ref "R15") (pin "1") (pinfunction "1_1") (pintype "passive"))
      (node (ref "R8") (pin "1") (pinfunction "1_1") (pintype "passive"))
    )
    (net (code "130") (name "Net-(C10-Pad2)") (class "Default")
      (node (ref "C10") (pin "2") (pinfunction "2_2") (pintype "passive"))
      (node (ref "R16") (pin "1") (pinfunction "1_1") (pintype "passive"))
      (node (ref "R9") (pin "1") (pinfunction "1_1") (pintype "passive"))
    )
    (net (code "131") (name "Net-(C11-Pad2)") (class "Default")
      (node (ref "C11") (pin "2") (pinfunction "2_2") (pintype "passive"))
      (node (ref "R10") (pin "1") (pinfunction "1_1") (pintype "passive"))
      (node (ref "R17") (pin "1") (pinfunction "1_1") (pintype "passive"))
    )
    (net (code "132") (name "Net-(C12-Pad2)") (class "Default")
      (node (ref "C12") (pin "2") (pinfunction "2_2") (pintype "passive"))
      (node (ref "R11") (pin "1") (pinfunction "1_1") (pintype "passive"))
      (node (ref "R18") (pin "1") (pinfunction "1_1") (pintype "passive"))
    )
    (net (code "133") (name "Net-(C27-Pad2)") (class "Default")
      (node (ref "C27") (pin "2") (pinfunction "2_2") (pintype "passive"))
      (node (ref "L2") (pin "1") (pinfunction "1_1") (pintype "passive"))
    )
    (net (code "134") (name "Net-(Card1-CLK)") (class "Default")
      (node (ref "Card1") (pin "3") (pinfunction "CLK_3") (pintype "power_in"))
      (node (ref "D16") (pin "5") (pintype "passive"))
      (node (ref "R44") (pin "1") (pinfunction "1_1") (pintype "passive"))
    )
    (net (code "135") (name "Net-(Card1-DATA)") (class "Default")
      (node (ref "Card1") (pin "6") (pinfunction "DATA_6") (pintype "power_in"))
      (node (ref "D16") (pin "6") (pintype "passive"))
      (node (ref "R46") (pin "1") (pinfunction "1_1") (pintype "passive"))
      (node (ref "R48") (pin "1") (pinfunction "1_1") (pintype "passive"))
    )
    (net (code "136") (name "Net-(Card1-RST)") (class "Default")
      (node (ref "Card1") (pin "2") (pinfunction "RST_2") (pintype "power_in"))
      (node (ref "D16") (pin "4") (pintype "passive"))
      (node (ref "R45") (pin "1") (pinfunction "1_1") (pintype "passive"))
    )
    (net (code "137") (name "Net-(Card1-VPP)") (class "Default")
      (node (ref "Card1") (pin "5") (pinfunction "VPP_5") (pintype "power_in"))
      (node (ref "D16") (pin "1") (pintype "passive"))
    )
    (net (code "138") (name "Net-(D2-A)") (class "Default")
      (node (ref "D2") (pin "1") (pinfunction "A_1") (pintype "passive"))
      (node (ref "F1") (pin "1") (pinfunction "1_1") (pintype "passive"))
      (node (ref "R12") (pin "1") (pinfunction "1_1") (pintype "passive"))
      (node (ref "R13") (pin "1") (pinfunction "1_1") (pintype "passive"))
    )
    (net (code "139") (name "Net-(D4-K)") (class "Default")
      (node (ref "D4") (pin "2") (pinfunction "K_2") (pintype "passive"))
      (node (ref "L1") (pin "1") (pinfunction "1_1") (pintype "passive"))
      (node (ref "U1") (pin "2") (pinfunction "OUT_2") (pintype "passive"))
    )
    (net (code "140") (name "Net-(D10-K)") (class "Default")
      (node (ref "D10") (pin "2") (pinfunction "K_2") (pintype "passive"))
      (node (ref "R51") (pin "2") (pinfunction "2_2") (pintype "passive"))
    )
    (net (code "141") (name "Net-(D11-A)") (class "Default")
      (node (ref "D11") (pin "1") (pinfunction "A_1") (pintype "passive"))
      (node (ref "R28") (pin "2") (pinfunction "2_2") (pintype "passive"))
    )
    (net (code "142") (name "Net-(D12-A)") (class "Default")
      (node (ref "D12") (pin "1") (pinfunction "A_1") (pintype "passive"))
      (node (ref "R29") (pin "1") (pinfunction "1_1") (pintype "passive"))
    )
    (net (code "143") (name "Net-(D14-K)") (class "Default")
      (node (ref "D14") (pin "2") (pinfunction "K_2") (pintype "passive"))
      (node (ref "R37") (pin "1") (pinfunction "1_1") (pintype "passive"))
    )
    (net (code "144") (name "Net-(D15-A)") (class "Default")
      (node (ref "D15") (pin "1") (pinfunction "A_1") (pintype "passive"))
      (node (ref "R40") (pin "2") (pinfunction "2_2") (pintype "passive"))
    )
    (net (code "145") (name "Net-(D15-K)") (class "Default")
      (node (ref "D15") (pin "2") (pinfunction "K_2") (pintype "passive"))
      (node (ref "Q7") (pin "3") (pinfunction "C_3") (pintype "passive"))
    )
    (net (code "146") (name "Net-(D17-K)") (class "Default")
      (node (ref "D17") (pin "2") (pinfunction "K_2") (pintype "passive"))
      (node (ref "R71") (pin "2") (pinfunction "2_2") (pintype "passive"))
    )
    (net (code "147") (name "Net-(D18-A)") (class "Default")
      (node (ref "D18") (pin "1") (pinfunction "A_1") (pintype "passive"))
      (node (ref "D9") (pin "2") (pinfunction "K_2") (pintype "passive"))
      (node (ref "R2") (pin "1") (pinfunction "1_1") (pintype "passive"))
      (node (ref "R26") (pin "1") (pinfunction "1_1") (pintype "passive"))
      (node (ref "U4") (pin "6") (pinfunction "A_6") (pintype "passive"))
    )
    (net (code "148") (name "Net-(D18-K)") (class "Default")
      (node (ref "D18") (pin "2") (pinfunction "K_2") (pintype "passive"))
      (node (ref "D6") (pin "2") (pinfunction "K_2") (pintype "passive"))
      (node (ref "R21") (pin "1") (pinfunction "1_1") (pintype "passive"))
      (node (ref "R3") (pin "1") (pinfunction "1_1") (pintype "passive"))
      (node (ref "U4") (pin "7") (pinfunction "B_7") (pintype "passive"))
    )
    (net (code "149") (name "Net-(D19-A)") (class "Default")
      (node (ref "D19") (pin "1") (pinfunction "A_1") (pintype "passive"))
      (node (ref "D8") (pin "2") (pinfunction "K_2") (pintype "passive"))
      (node (ref "R25") (pin "1") (pinfunction "1_1") (pintype "passive"))
      (node (ref "R72") (pin "1") (pinfunction "1_1") (pintype "passive"))
      (node (ref "U3") (pin "6") (pinfunction "A_6") (pintype "passive"))
    )
    (net (code "150") (name "Net-(D19-K)") (class "Default")
      (node (ref "D19") (pin "2") (pinfunction "K_2") (pintype "passive"))
      (node (ref "D5") (pin "2") (pinfunction "K_2") (pintype "passive"))
      (node (ref "R20") (pin "1") (pinfunction "1_1") (pintype "passive"))
      (node (ref "R73") (pin "2") (pinfunction "2_2") (pintype "passive"))
      (node (ref "U3") (pin "7") (pinfunction "B_7") (pintype "passive"))
    )
    (net (code "151") (name "Net-(E1-A)") (class "Default")
      (node (ref "C27") (pin "1") (pinfunction "1_1") (pintype "passive"))
      (node (ref "E1") (pin "1") (pinfunction "A_1") (pintype "passive"))
    )
    (net (code "152") (name "Net-(E2-A)") (class "Default")
      (node (ref "C30") (pin "2") (pinfunction "2_2") (pintype "passive"))
      (node (ref "E2") (pin "1") (pinfunction "A_1") (pintype "passive"))
      (node (ref "R52") (pin "2") (pinfunction "2_2") (pintype "passive"))
    )
    (net (code "153") (name "Net-(LED1-K)") (class "Default")
      (node (ref "LED1") (pin "2") (pinfunction "K_2") (pintype "passive"))
      (node (ref "R41") (pin "1") (pinfunction "1_1") (pintype "passive"))
    )
    (net (code "154") (name "Net-(Q3-B)") (class "Default")
      (node (ref "Q3") (pin "2") (pinfunction "B_2") (pintype "passive"))
      (node (ref "Q8") (pin "2") (pinfunction "B_2") (pintype "passive"))
      (node (ref "R32") (pin "2") (pinfunction "2_2") (pintype "passive"))
      (node (ref "R34") (pin "1") (pinfunction "1_1") (pintype "passive"))
    )
    (net (code "155") (name "Net-(Q4-B)") (class "Default")
      (node (ref "Q4") (pin "1") (pinfunction "B_1") (pintype "passive"))
      (node (ref "R49") (pin "2") (pinfunction "2_2") (pintype "passive"))
      (node (ref "R50") (pin "1") (pinfunction "1_1") (pintype "passive"))
    )
    (net (code "156") (name "Net-(Q4-C)") (class "Default")
      (node (ref "Q4") (pin "3") (pinfunction "C_3") (pintype "passive"))
      (node (ref "R51") (pin "1") (pinfunction "1_1") (pintype "passive"))
    )
    (net (code "157") (name "Net-(Q5-B)") (class "Default")
      (node (ref "Q5") (pin "2") (pinfunction "B_2") (pintype "passive"))
      (node (ref "R37") (pin "2") (pinfunction "2_2") (pintype "passive"))
      (node (ref "R39") (pin "2") (pinfunction "2_2") (pintype "passive"))
    )
    (net (code "158") (name "Net-(Q5-C)") (class "Default")
      (node (ref "Q5") (pin "3") (pinfunction "C_3") (pintype "passive"))
      (node (ref "R34") (pin "2") (pinfunction "2_2") (pintype "passive"))
    )
    (net (code "159") (name "Net-(Q7-B)") (class "Default")
      (node (ref "Q7") (pin "1") (pinfunction "B_1") (pintype "passive"))
      (node (ref "R42") (pin "1") (pinfunction "1_1") (pintype "passive"))
    )
    (net (code "160") (name "Net-(Q9-B)") (class "Default")
      (node (ref "Q9") (pin "1") (pinfunction "B_1") (pintype "passive"))
      (node (ref "R54") (pin "2") (pinfunction "2_2") (pintype "passive"))
    )
    (net (code "161") (name "Net-(Q10-B)") (class "Default")
      (node (ref "Q10") (pin "1") (pinfunction "B_1") (pintype "passive"))
      (node (ref "R56") (pin "2") (pinfunction "2_2") (pintype "passive"))
    )
    (net (code "162") (name "Net-(Q11-B)") (class "Default")
      (node (ref "Q11") (pin "1") (pinfunction "B_1") (pintype "passive"))
      (node (ref "R58") (pin "2") (pinfunction "2_2") (pintype "passive"))
    )
    (net (code "163") (name "Net-(Q12-B)") (class "Default")
      (node (ref "Q12") (pin "1") (pinfunction "B_1") (pintype "passive"))
      (node (ref "R60") (pin "2") (pinfunction "2_2") (pintype "passive"))
    )
    (net (code "164") (name "Net-(Q14-B)") (class "Default")
      (node (ref "Q14") (pin "1") (pinfunction "B_1") (pintype "passive"))
      (node (ref "R63") (pin "1") (pinfunction "1_1") (pintype "passive"))
      (node (ref "R64") (pin "2") (pinfunction "2_2") (pintype "passive"))
    )
    (net (code "165") (name "Net-(Q15-B)") (class "Default")
      (node (ref "Q15") (pin "1") (pinfunction "B_1") (pintype "passive"))
      (node (ref "R65") (pin "1") (pinfunction "1_1") (pintype "passive"))
      (node (ref "R66") (pin "2") (pinfunction "2_2") (pintype "passive"))
    )
    (net (code "166") (name "Net-(Q16-B)") (class "Default")
      (node (ref "Q16") (pin "1") (pinfunction "B_1") (pintype "passive"))
      (node (ref "R68") (pin "2") (pinfunction "2_2") (pintype "passive"))
    )
    (net (code "167") (name "Net-(Q17-B)") (class "Default")
      (node (ref "Q17") (pin "1") (pinfunction "B_1") (pintype "passive"))
      (node (ref "R69") (pin "2") (pinfunction "2_2") (pintype "passive"))
      (node (ref "R70") (pin "1") (pinfunction "1_1") (pintype "passive"))
    )
    (net (code "168") (name "Net-(Q17-C)") (class "Default")
      (node (ref "Q17") (pin "3") (pinfunction "C_3") (pintype "passive"))
      (node (ref "R71") (pin "1") (pinfunction "1_1") (pintype "passive"))
    )
    (net (code "169") (name "Net-(U1-BACK)") (class "Default")
      (node (ref "R1") (pin "2") (pinfunction "2_2") (pintype "passive"))
      (node (ref "U1") (pin "4") (pinfunction "BACK_4") (pintype "passive"))
    )
    (net (code "170") (name "Net-(U7-RFIN)") (class "Default")
      (node (ref "L2") (pin "2") (pinfunction "2_2") (pintype "passive"))
      (node (ref "U7") (pin "3") (pinfunction "RFIN_3") (pintype "passive"))
    )
    (net (code "171") (name "VBAT") (class "Default")
      (node (ref "C19") (pin "1") (pinfunction "1_1") (pintype "passive"))
      (node (ref "C20") (pin "2") (pinfunction "2_2") (pintype "passive"))
      (node (ref "C21") (pin "2") (pinfunction "2_2") (pintype "passive"))
      (node (ref "C22") (pin "2") (pinfunction "2_2") (pintype "passive"))
      (node (ref "C23") (pin "2") (pinfunction "2_2") (pintype "passive"))
      (node (ref "C3") (pin "2") (pinfunction "2_2") (pintype "passive"))
      (node (ref "C4") (pin "1") (pinfunction "1_1") (pintype "passive"))
      (node (ref "D3") (pin "1") (pinfunction "A_1") (pintype "passive"))
      (node (ref "L1") (pin "2") (pinfunction "2_2") (pintype "passive"))
      (node (ref "R1") (pin "1") (pinfunction "1_1") (pintype "passive"))
      (node (ref "R38") (pin "2") (pinfunction "2_2") (pintype "passive"))
      (node (ref "R40") (pin "1") (pinfunction "1_1") (pintype "passive"))
      (node (ref "U8") (pin "20") (pinfunction "VBAT_20") (pintype "passive"))
      (node (ref "U8") (pin "21") (pinfunction "VBAT_21") (pintype "passive"))
      (node (ref "U8") (pin "22") (pinfunction "VBAT_22") (pintype "passive"))
    )
    (net (code "172") (name "VCC") (class "Default")
      (node (ref "C28") (pin "2") (pinfunction "2_2") (pintype "passive"))
      (node (ref "C31") (pin "2") (pinfunction "2_2") (pintype "passive"))
      (node (ref "C32") (pin "2") (pinfunction "2_2") (pintype "passive"))
      (node (ref "C5") (pin "2") (pinfunction "2_2") (pintype "passive"))
      (node (ref "CPU1") (pin "100") (pinfunction "VDD_3_100") (pintype "power_in"))
      (node (ref "CPU1") (pin "11") (pinfunction "VDD_5_11") (pintype "power_in"))
      (node (ref "CPU1") (pin "21") (pinfunction "VREF+_21") (pintype "power_in"))
      (node (ref "CPU1") (pin "22") (pinfunction "VDDA_22") (pintype "power_in"))
      (node (ref "CPU1") (pin "28") (pinfunction "VDD_4_28") (pintype "power_in"))
      (node (ref "CPU1") (pin "50") (pinfunction "VDD_1_50") (pintype "power_in"))
      (node (ref "CPU1") (pin "75") (pinfunction "VDD_2_75") (pintype "power_in"))
      (node (ref "D1") (pin "1") (pinfunction "1_1") (pintype "passive"))
      (node (ref "D10") (pin "1") (pinfunction "A_1") (pintype "passive"))
      (node (ref "D17") (pin "1") (pinfunction "A_1") (pintype "passive"))
      (node (ref "D3") (pin "2") (pinfunction "K_2") (pintype "passive"))
      (node (ref "P1") (pin "6") (pinfunction "6_6") (pintype "passive"))
      (node (ref "P10") (pin "6") (pinfunction "6_6") (pintype "passive"))
      (node (ref "P11") (pin "1") (pinfunction "1_1") (pintype "passive"))
      (node (ref "P12") (pin "1") (pinfunction "1_1") (pintype "passive"))
      (node (ref "P13") (pin "1") (pinfunction "1_1") (pintype "passive"))
      (node (ref "P14") (pin "1") (pinfunction "1_1") (pintype "passive"))
      (node (ref "P3") (pin "1") (pinfunction "1_1") (pintype "passive"))
      (node (ref "P4") (pin "1") (pinfunction "1_1") (pintype "passive"))
      (node (ref "P8") (pin "7") (pinfunction "7_7") (pintype "passive"))
      (node (ref "P9") (pin "15") (pinfunction "15_15") (pintype "passive"))
      (node (ref "R2") (pin "2") (pinfunction "2_2") (pintype "passive"))
      (node (ref "R23") (pin "1") (pinfunction "1_1") (pintype "passive"))
      (node (ref "R24") (pin "1") (pinfunction "1_1") (pintype "passive"))
      (node (ref "R29") (pin "2") (pinfunction "2_2") (pintype "passive"))
      (node (ref "R43") (pin "1") (pinfunction "1_1") (pintype "passive"))
      (node (ref "R53") (pin "1") (pinfunction "1_1") (pintype "passive"))
      (node (ref "R57") (pin "1") (pinfunction "1_1") (pintype "passive"))
      (node (ref "R72") (pin "2") (pinfunction "2_2") (pintype "passive"))
      (node (ref "U2") (pin "3") (pinfunction "Vin_3") (pintype "passive"))
      (node (ref "U3") (pin "8") (pinfunction "VCC_8") (pintype "passive"))
      (node (ref "U4") (pin "8") (pinfunction "VCC_8") (pintype "passive"))
      (node (ref "U6") (pin "10") (pinfunction "10_10") (pintype "passive"))
      (node (ref "U7") (pin "4") (pinfunction "VCC_4") (pintype "passive"))
      (node (ref "U7") (pin "5") (pinfunction "SHDN_5") (pintype "passive"))
    )
    (net (code "173") (name "unconnected-(CPU1-NC-Pad73)") (class "Default")
      (node (ref "CPU1") (pin "73") (pinfunction "NC_73") (pintype "passive"))
    )
    (net (code "174") (name "unconnected-(CPU1-VBAT-Pad6)") (class "Default")
      (node (ref "CPU1") (pin "6") (pinfunction "VBAT_6") (pintype "power_in"))
    )
    (net (code "175") (name "unconnected-(Card1-GND-Pad4)") (class "Default")
      (node (ref "Card1") (pin "4") (pinfunction "GND_4") (pintype "passive"))
    )
    (net (code "176") (name "unconnected-(P10-Pad3)") (class "Default")
      (node (ref "P10") (pin "3") (pinfunction "3_3") (pintype "passive"))
    )
    (net (code "177") (name "unconnected-(P10-Pad4)") (class "Default")
      (node (ref "P10") (pin "4") (pinfunction "4_4") (pintype "passive"))
    )
    (net (code "178") (name "unconnected-(P10-Pad5)") (class "Default")
      (node (ref "P10") (pin "5") (pinfunction "5_5") (pintype "passive"))
    )
    (net (code "179") (name "unconnected-(P10-Pad9)") (class "Default")
      (node (ref "P10") (pin "9") (pinfunction "9_9") (pintype "passive"))
    )
    (net (code "180") (name "unconnected-(P10-Pad10)") (class "Default")
      (node (ref "P10") (pin "10") (pinfunction "10_10") (pintype "passive"))
    )
    (net (code "181") (name "unconnected-(P13-Pad6)") (class "Default")
      (node (ref "P13") (pin "6") (pinfunction "6_6") (pintype "passive"))
    )
    (net (code "182") (name "unconnected-(P13-Pad10)") (class "Default")
      (node (ref "P13") (pin "10") (pinfunction "10_10") (pintype "passive"))
    )
    (net (code "183") (name "unconnected-(U6-Pad6)") (class "Default")
      (node (ref "U6") (pin "6") (pinfunction "6_6") (pintype "passive"))
    )
    (net (code "184") (name "unconnected-(U8-ADC1-Pad2)") (class "Default")
      (node (ref "U8") (pin "2") (pinfunction "ADC1_2") (pintype "passive"))
    )
    (net (code "185") (name "unconnected-(U8-ADC2-Pad3)") (class "Default")
      (node (ref "U8") (pin "3") (pinfunction "ADC2_3") (pintype "passive"))
    )
    (net (code "186") (name "unconnected-(U8-FORCE_USB_BOOT-Pad16)") (class "Default")
      (node (ref "U8") (pin "16") (pinfunction "FORCE_USB_BOOT_16") (pintype "passive"))
    )
    (net (code "187") (name "unconnected-(U8-GPIO1-Pad5)") (class "Default")
      (node (ref "U8") (pin "5") (pinfunction "GPIO1_5") (pintype "passive"))
    )
    (net (code "188") (name "unconnected-(U8-GPIO2-Pad6)") (class "Default")
      (node (ref "U8") (pin "6") (pinfunction "GPIO2_6") (pintype "passive"))
    )
    (net (code "189") (name "unconnected-(U8-GPIO3-Pad7)") (class "Default")
      (node (ref "U8") (pin "7") (pinfunction "GPIO3_7") (pintype "passive"))
    )
    (net (code "190") (name "unconnected-(U8-I2C_SCL-Pad44)") (class "Default")
      (node (ref "U8") (pin "44") (pinfunction "I2C_SCL_44") (pintype "passive"))
    )
    (net (code "191") (name "unconnected-(U8-I2C_SDA-Pad43)") (class "Default")
      (node (ref "U8") (pin "43") (pinfunction "I2C_SDA_43") (pintype "passive"))
    )
    (net (code "192") (name "unconnected-(U8-I2S_MCLK-Pad49)") (class "Default")
      (node (ref "U8") (pin "49") (pinfunction "I2S_MCLK_49") (pintype "passive"))
    )
    (net (code "193") (name "unconnected-(U8-PCM_CLK-Pad46)") (class "Default")
      (node (ref "U8") (pin "46") (pinfunction "PCM_CLK_46") (pintype "passive"))
    )
    (net (code "194") (name "unconnected-(U8-PCM_DIN-Pad47)") (class "Default")
      (node (ref "U8") (pin "47") (pinfunction "PCM_DIN_47") (pintype "passive"))
    )
    (net (code "195") (name "unconnected-(U8-PCM_DOUT-Pad48)") (class "Default")
      (node (ref "U8") (pin "48") (pinfunction "PCM_DOUT_48") (pintype "passive"))
    )
    (net (code "196") (name "unconnected-(U8-PCM_SYNC-Pad45)") (class "Default")
      (node (ref "U8") (pin "45") (pinfunction "PCM_SYNC_45") (pintype "passive"))
    )
    (net (code "197") (name "unconnected-(U8-RF_ANT_MAIN-Pad67)") (class "Default")
      (node (ref "U8") (pin "67") (pinfunction "RF_ANT_MAIN_67") (pintype "passive"))
    )
    (net (code "198") (name "unconnected-(U8-SDC-DATA0-Pad38)") (class "Default")
      (node (ref "U8") (pin "38") (pinfunction "SDC-DATA0_38") (pintype "passive"))
    )
    (net (code "199") (name "unconnected-(U8-SDC-DATA1-Pad39)") (class "Default")
      (node (ref "U8") (pin "39") (pinfunction "SDC-DATA1_39") (pintype "passive"))
    )
    (net (code "200") (name "unconnected-(U8-SDC-DATA2-Pad40)") (class "Default")
      (node (ref "U8") (pin "40") (pinfunction "SDC-DATA2_40") (pintype "passive"))
    )
    (net (code "201") (name "unconnected-(U8-SDC-DATA3-Pad41)") (class "Default")
      (node (ref "U8") (pin "41") (pinfunction "SDC-DATA3_41") (pintype "passive"))
    )
    (net (code "202") (name "unconnected-(U8-SDC_CLK-Pad37)") (class "Default")
      (node (ref "U8") (pin "37") (pinfunction "SDC_CLK_37") (pintype "passive"))
    )
    (net (code "203") (name "unconnected-(U8-SDC_CMD-Pad36)") (class "Default")
      (node (ref "U8") (pin "36") (pinfunction "SDC_CMD_36") (pintype "passive"))
    )
    (net (code "204") (name "unconnected-(U8-SIM_SELECT-Pad8)") (class "Default")
      (node (ref "U8") (pin "8") (pinfunction "SIM_SELECT_8") (pintype "passive"))
    )
    (net (code "205") (name "unconnected-(U8-SPI_CLK-Pad62)") (class "Default")
      (node (ref "U8") (pin "62") (pinfunction "SPI_CLK_62") (pintype "passive"))
    )
    (net (code "206") (name "unconnected-(U8-SPI_CS_N-Pad65)") (class "Default")
      (node (ref "U8") (pin "65") (pinfunction "SPI_CS_N_65") (pintype "passive"))
    )
    (net (code "207") (name "unconnected-(U8-SPI_MISO-Pad63)") (class "Default")
      (node (ref "U8") (pin "63") (pinfunction "SPI_MISO_63") (pintype "passive"))
    )
    (net (code "208") (name "unconnected-(U8-SPI_MOSI-Pad64)") (class "Default")
      (node (ref "U8") (pin "64") (pinfunction "SPI_MOSI_64") (pintype "passive"))
    )
    (net (code "209") (name "unconnected-(U8-UART1_CTS-Pad59)") (class "Default")
      (node (ref "U8") (pin "59") (pinfunction "UART1_CTS_59") (pintype "passive"))
    )
    (net (code "210") (name "unconnected-(U8-UART1_RTS-Pad58)") (class "Default")
      (node (ref "U8") (pin "58") (pinfunction "UART1_RTS_58") (pintype "passive"))
    )
    (net (code "211") (name "unconnected-(U8-UART1_RX-Pad60)") (class "Default")
      (node (ref "U8") (pin "60") (pinfunction "UART1_RX_60") (pintype "passive"))
    )
    (net (code "212") (name "unconnected-(U8-UART1_TX-Pad61)") (class "Default")
      (node (ref "U8") (pin "61") (pinfunction "UART1_TX_61") (pintype "passive"))
    )
    (net (code "213") (name "unconnected-(U8-USB_HS_DM-Pad26)") (class "Default")
      (node (ref "U8") (pin "26") (pinfunction "USB_HS_DM_26") (pintype "passive"))
    )
    (net (code "214") (name "unconnected-(U8-USB_HS_DP-Pad27)") (class "Default")
      (node (ref "U8") (pin "27") (pinfunction "USB_HS_DP_27") (pintype "passive"))
    )
    (net (code "215") (name "unconnected-(U8-USB_ID-Pad28)") (class "Default")
      (node (ref "U8") (pin "28") (pinfunction "USB_ID_28") (pintype "passive"))
    )
    (net (code "216") (name "unconnected-(U8-USB_VBUS-Pad25)") (class "Default")
      (node (ref "U8") (pin "25") (pinfunction "USB_VBUS_25") (pintype "passive"))
    )
  )
)
